# veils_v110.net
KiCad netlist of a schematic drawn in EAGLE
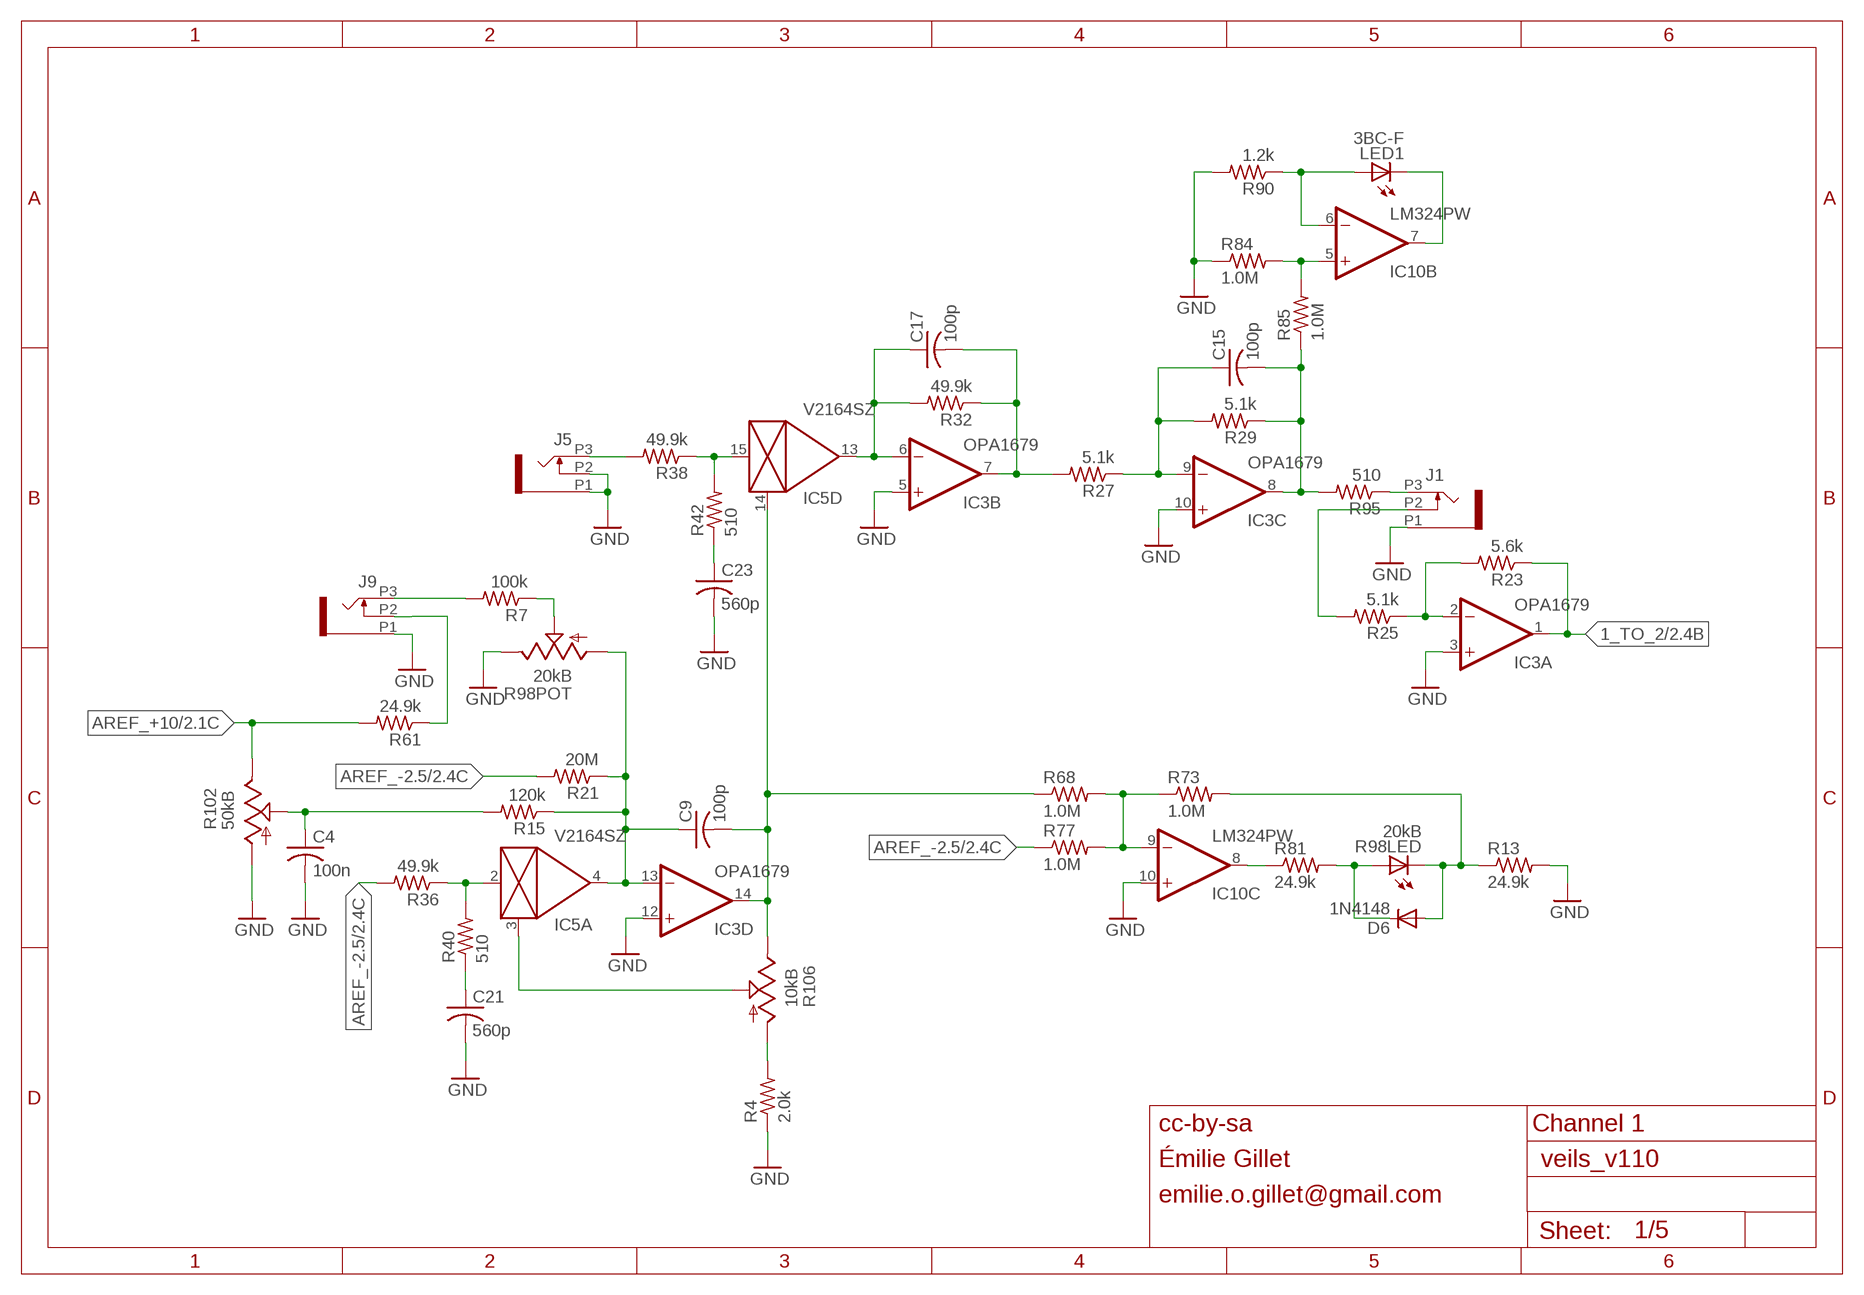
[diagram p0: schematic, sheet 1]
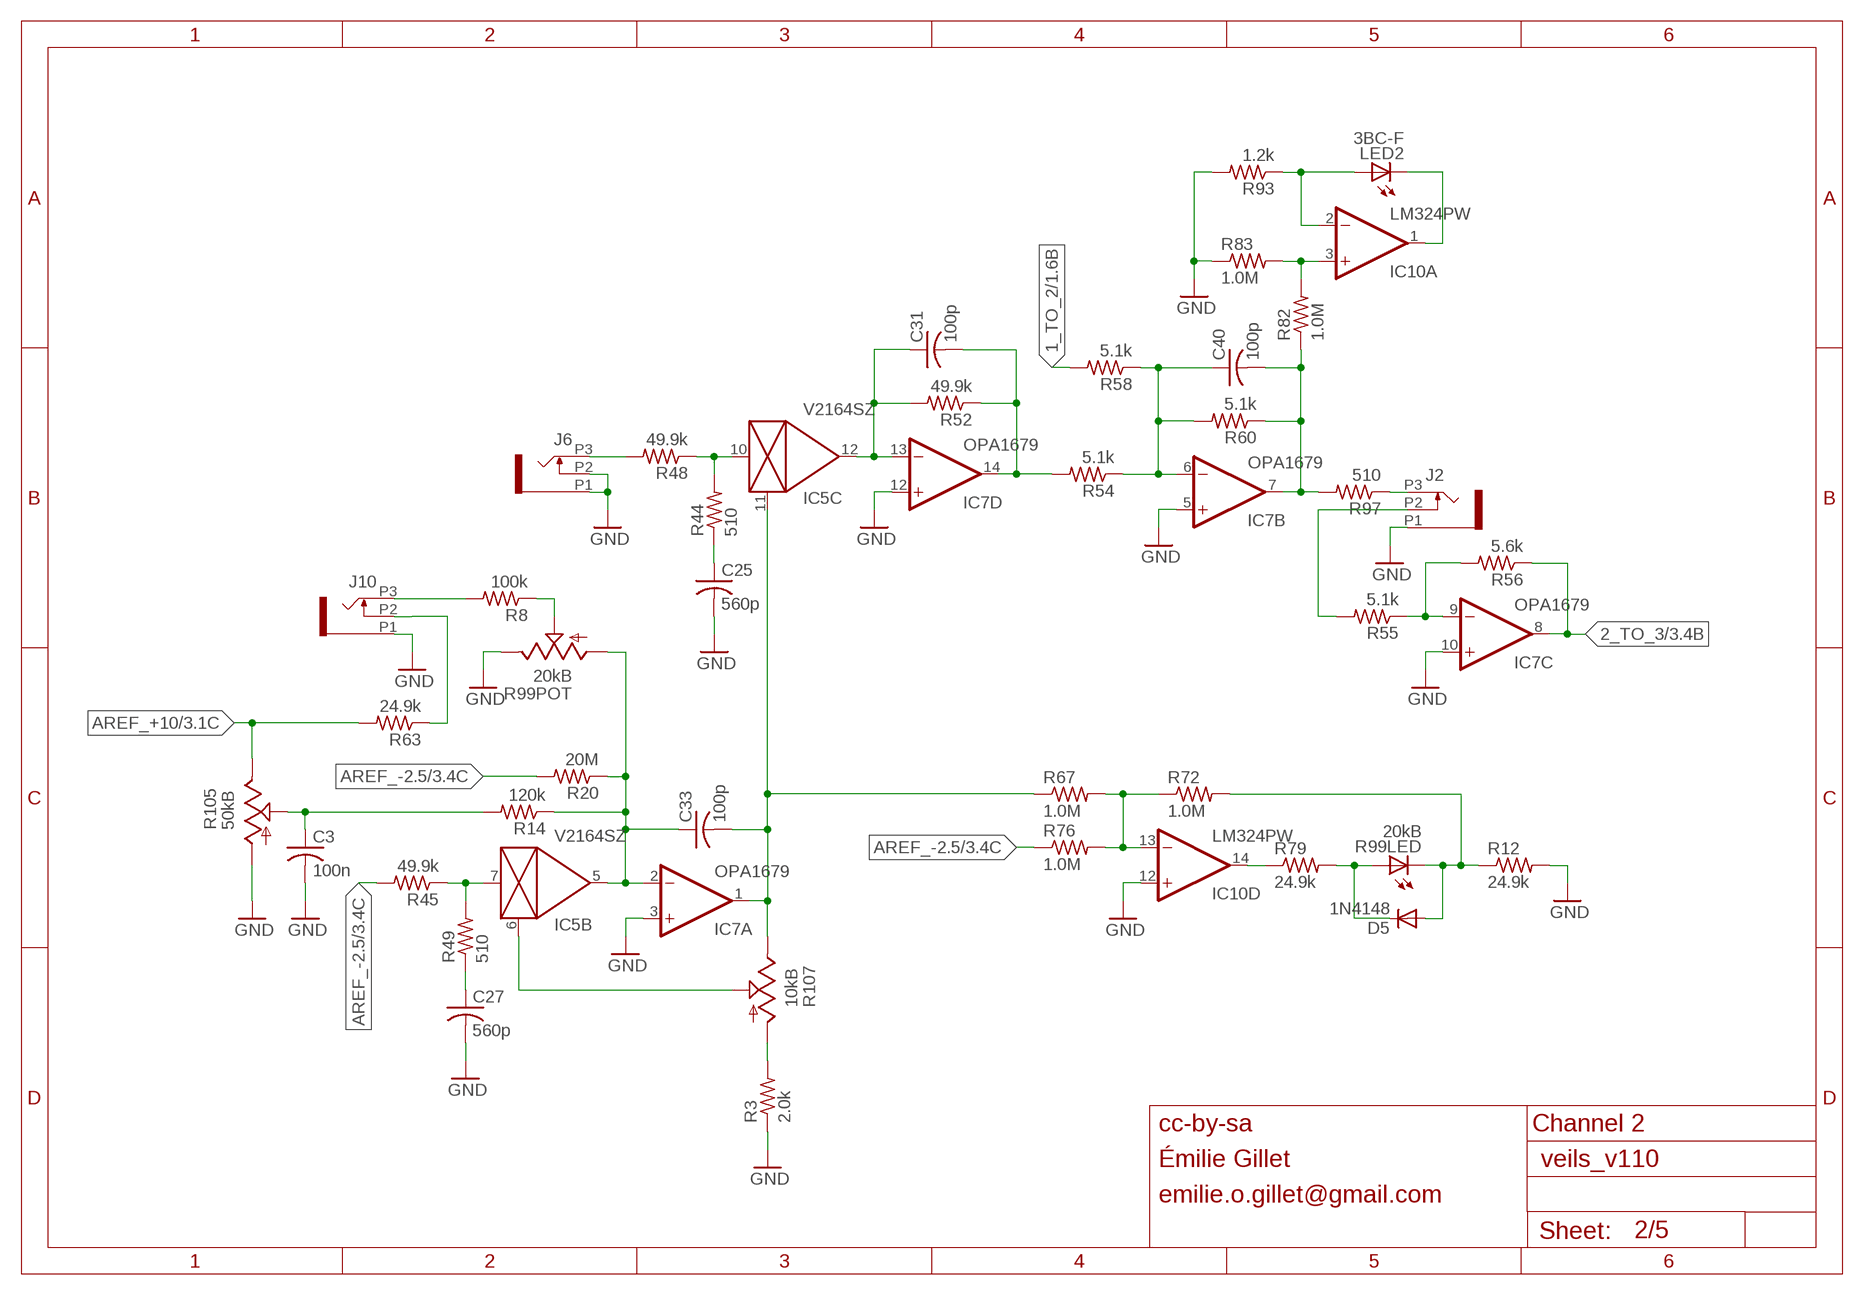
[diagram p1: schematic, sheet 2]
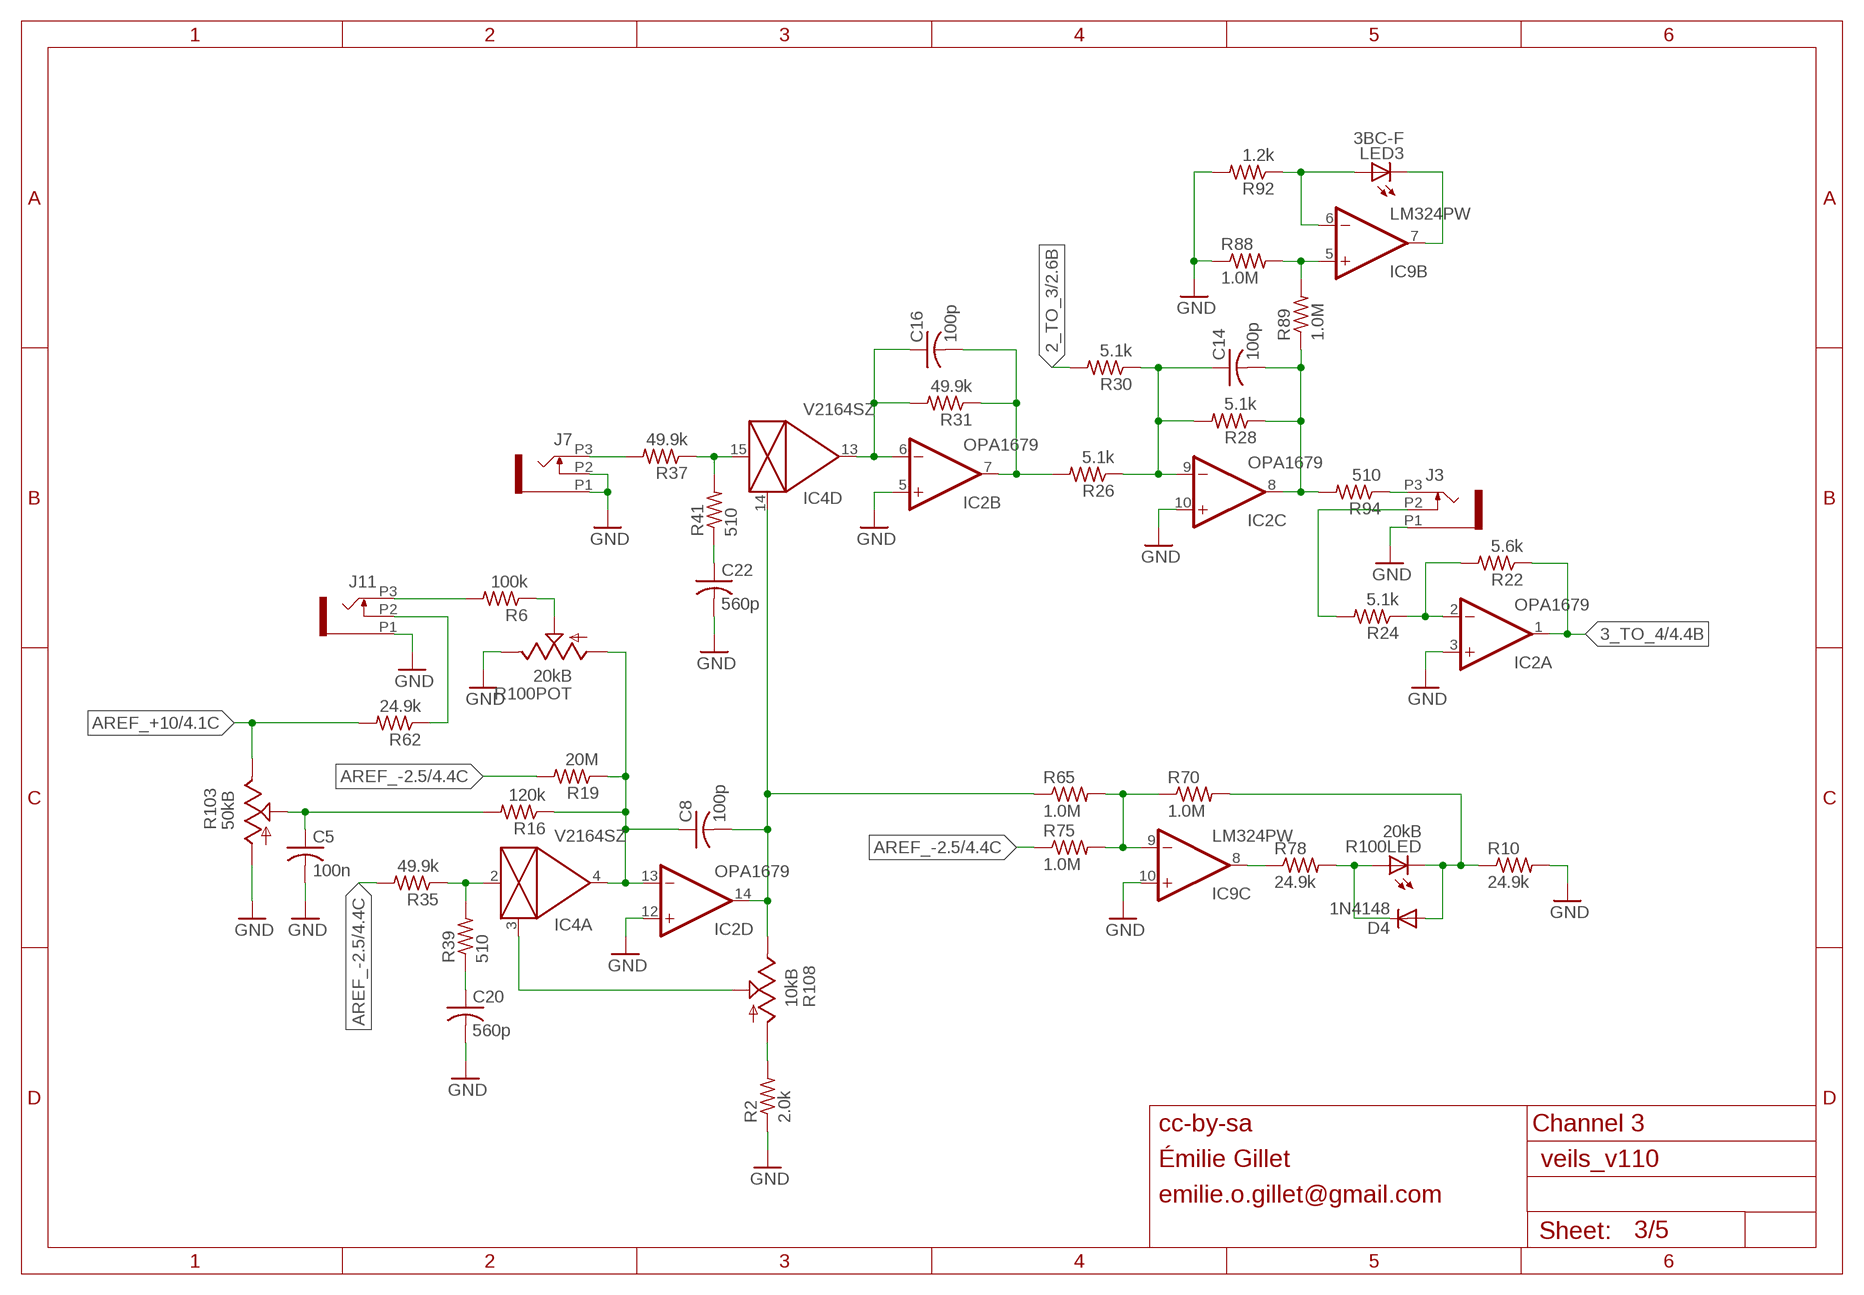
[diagram p2: schematic, sheet 3]
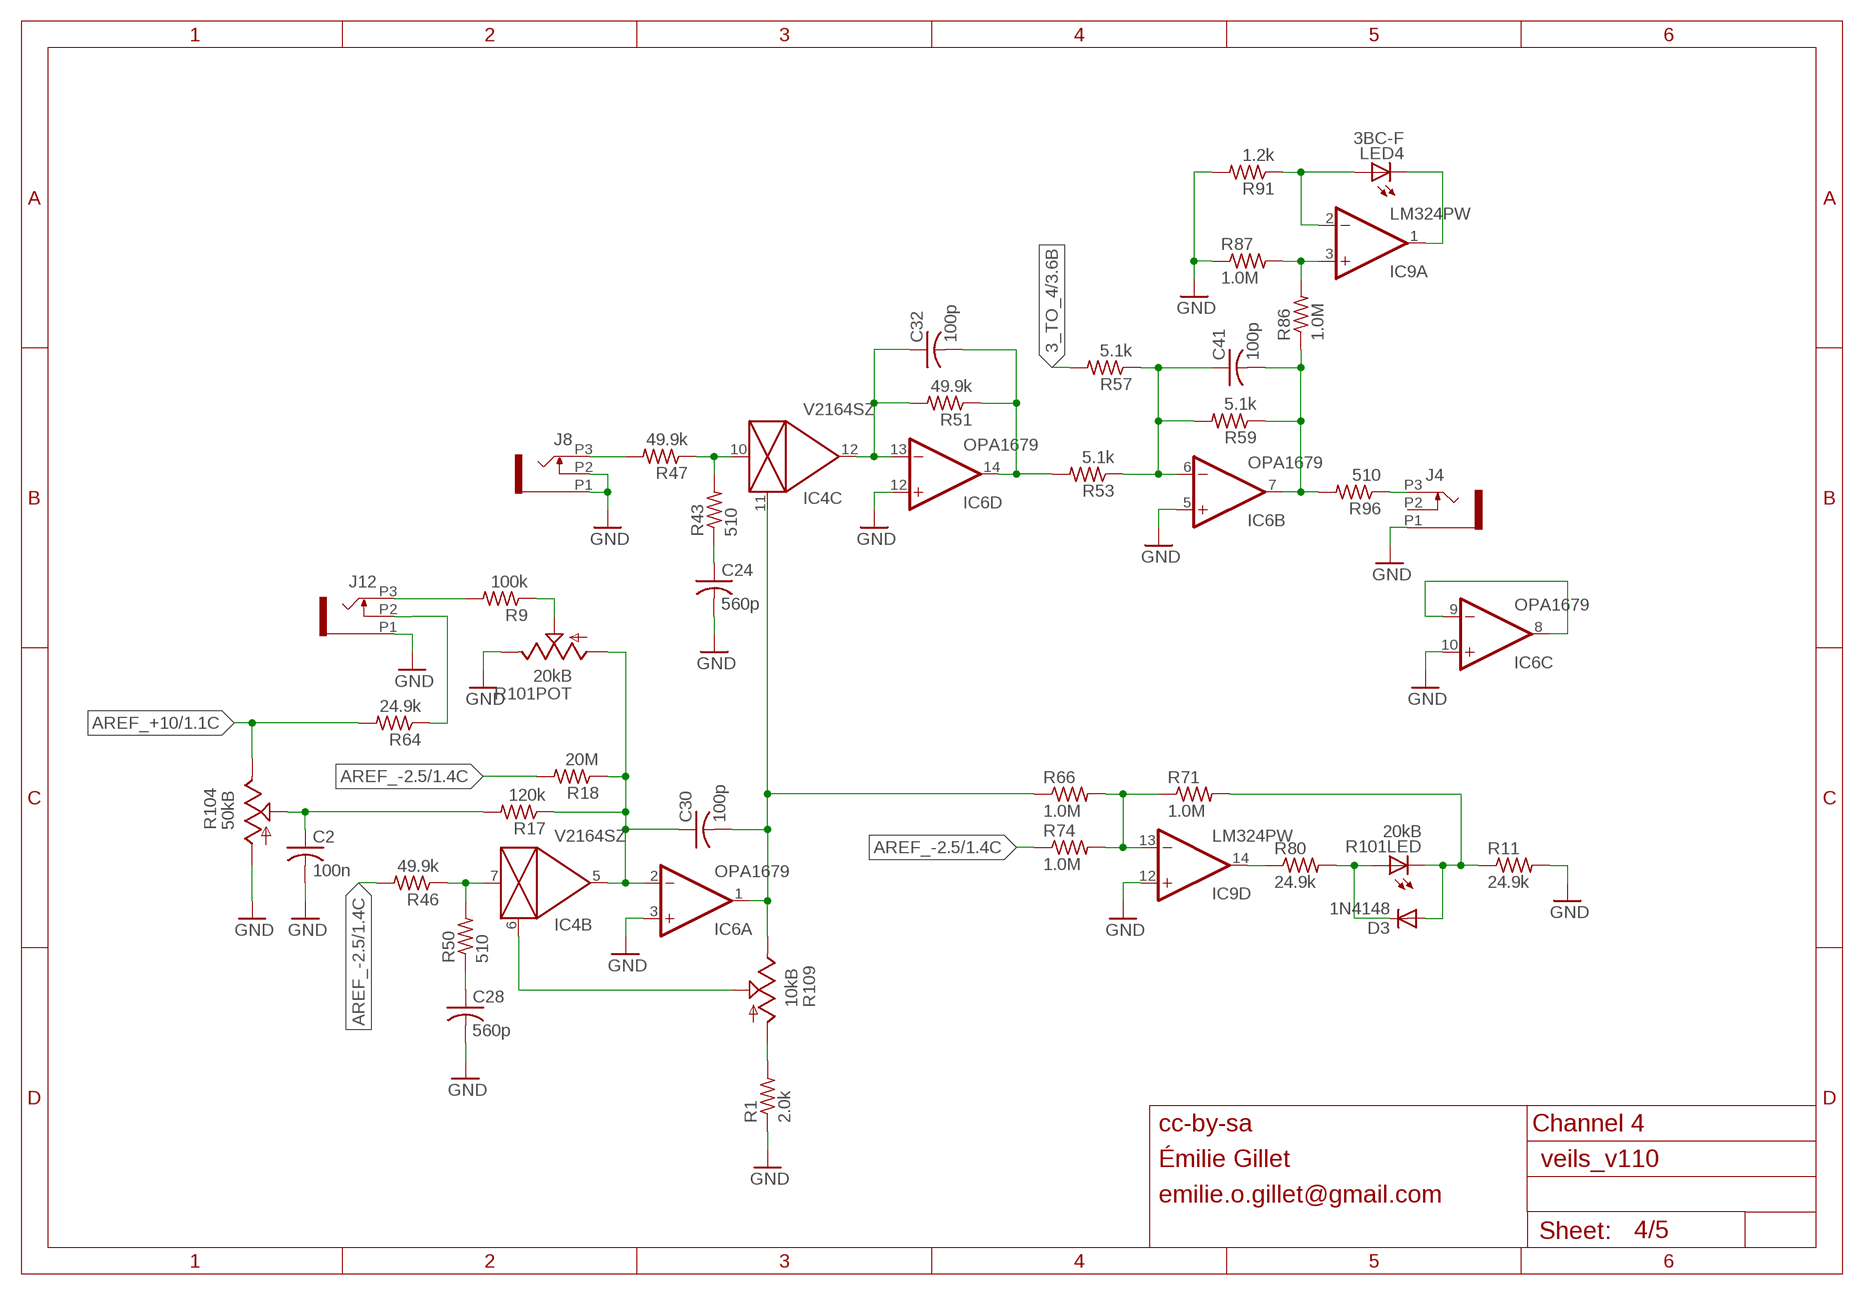
[diagram p3: schematic, sheet 4]
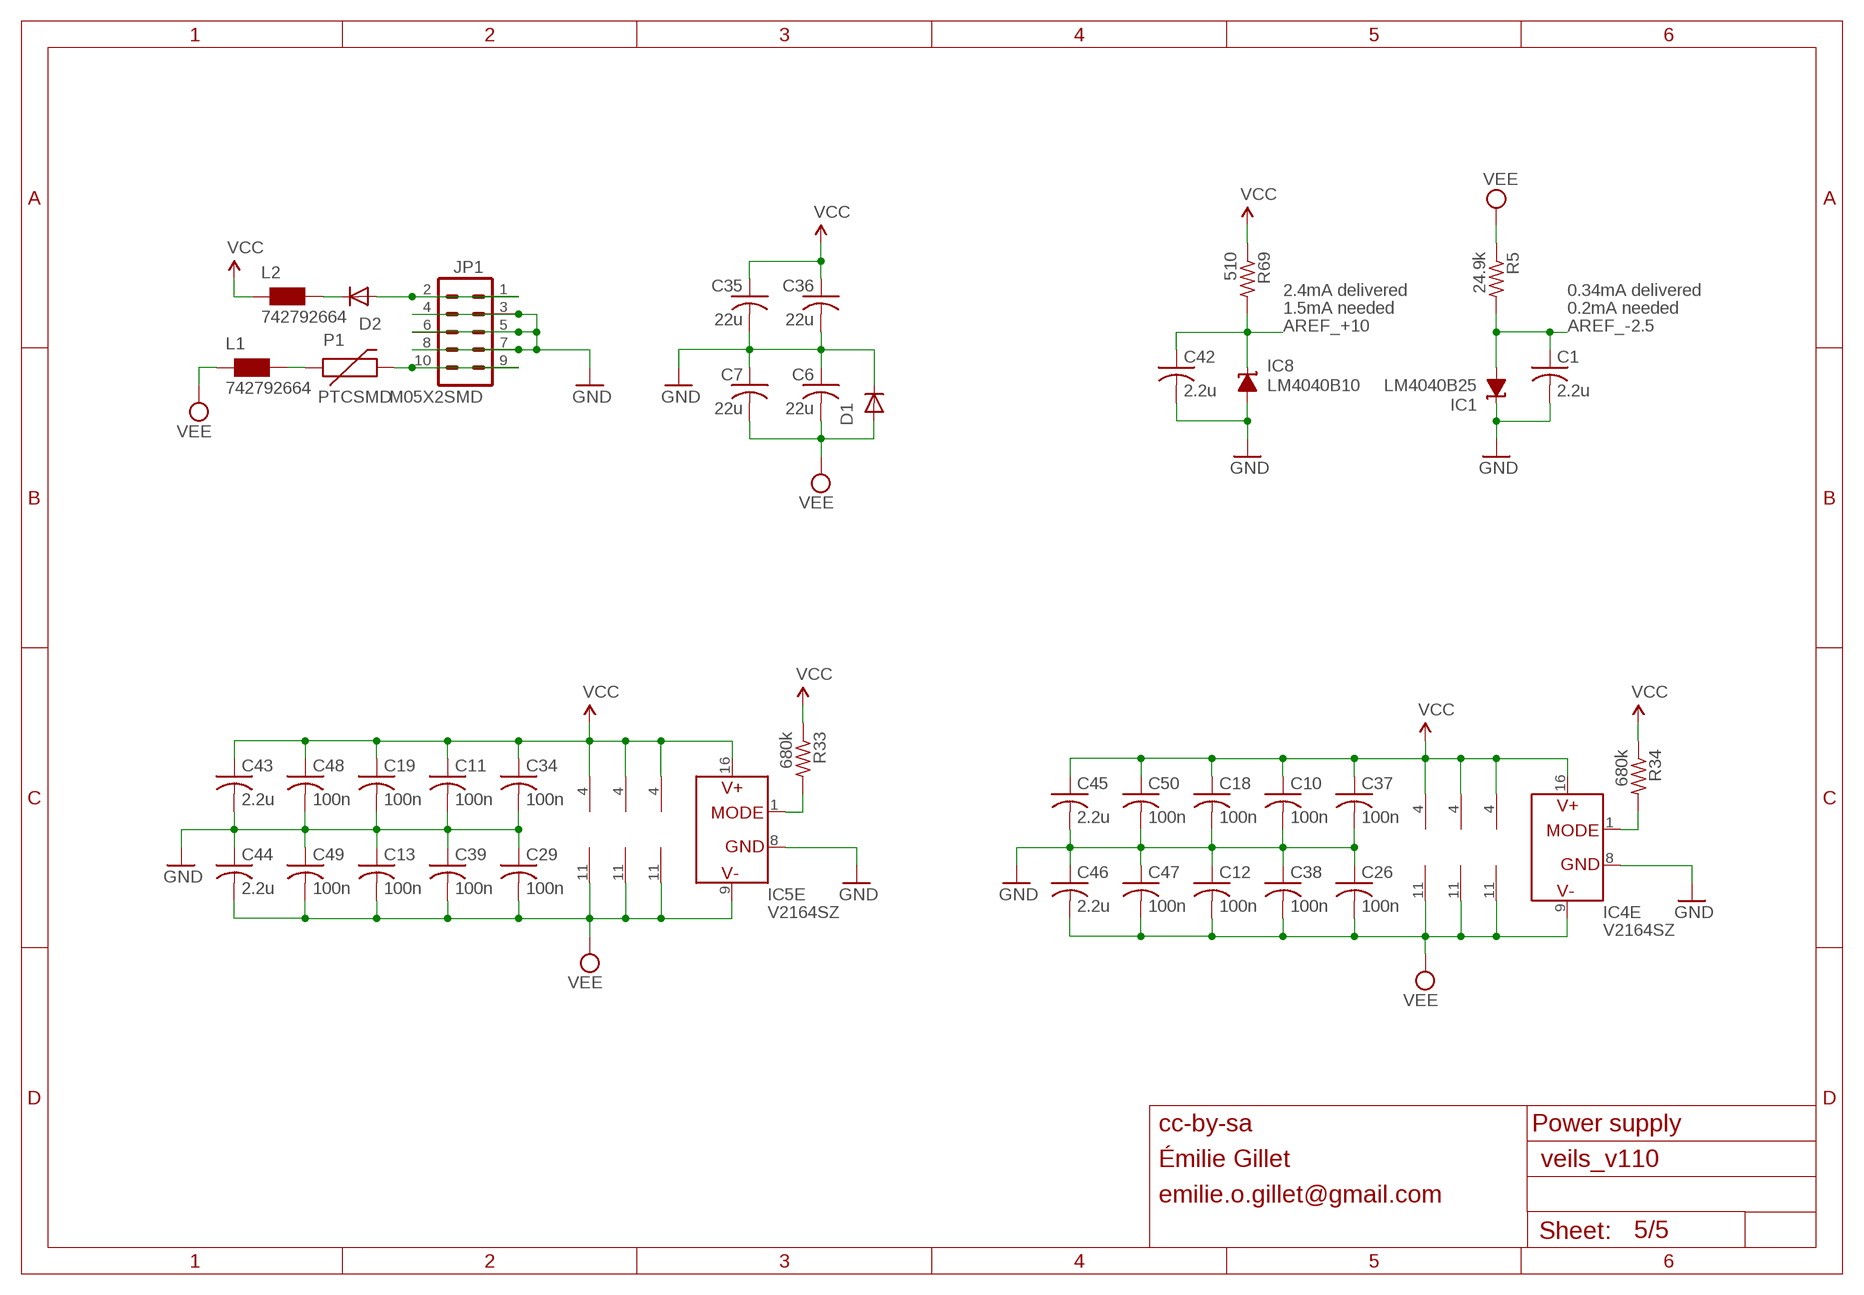
[diagram p4: schematic, sheet 5]

(export (version "E")
  (design (tool "Eeschema 10.0.6"))
  (components
    (comp (ref "C3")
      (value "100n")
      (footprint "eagle-import:C0402")
      (libsource (lib "eagle-import") (part "C-USC0402"))
    )
    (comp (ref "C25")
      (value "560p")
      (footprint "eagle-import:C0402")
      (libsource (lib "eagle-import") (part "C-USC0402"))
    )
    (comp (ref "C27")
      (value "560p")
      (footprint "eagle-import:C0402")
      (libsource (lib "eagle-import") (part "C-USC0402"))
    )
    (comp (ref "C31")
      (value "100p")
      (footprint "eagle-import:C0402")
      (libsource (lib "eagle-import") (part "C-USC0402"))
    )
    (comp (ref "C33")
      (value "100p")
      (footprint "eagle-import:C0402")
      (libsource (lib "eagle-import") (part "C-USC0402"))
    )
    (comp (ref "C40")
      (value "100p")
      (footprint "eagle-import:C0402")
      (libsource (lib "eagle-import") (part "C-USC0402"))
    )
    (comp (ref "D5")
      (value "1N4148")
      (footprint "eagle-import:SOD523")
      (libsource (lib "eagle-import") (part "DIODE-SOD523"))
    )
    (comp (ref "IC5")
      (value "V2164SZ")
      (footprint "eagle-import:SOIC16N")
      (libsource (lib "eagle-import") (part "SSM2164S"))
    )
    (comp (ref "IC7")
      (value "OPA1679")
      (footprint "eagle-import:TSSOP14_065")
      (libsource (lib "eagle-import") (part "OPA1679PW"))
    )
    (comp (ref "IC10")
      (value "LM324PW")
      (footprint "eagle-import:TSSOP14_065")
      (libsource (lib "eagle-import") (part "TL074PW"))
    )
    (comp (ref "J2")
      (value "PJ301_THONKICONNTME")
      (footprint "eagle-import:WQP_PJ_301M_TME")
      (libsource (lib "eagle-import") (part "PJ301_THONKICONNTME"))
    )
    (comp (ref "J6")
      (value "PJ301_THONKICONNTME")
      (footprint "eagle-import:WQP_PJ_301M_TME")
      (libsource (lib "eagle-import") (part "PJ301_THONKICONNTME"))
    )
    (comp (ref "J10")
      (value "PJ301_THONKICONNTME")
      (footprint "eagle-import:WQP_PJ_301M_TME")
      (libsource (lib "eagle-import") (part "PJ301_THONKICONNTME"))
    )
    (comp (ref "LED2")
      (value "3BC-F")
      (footprint "eagle-import:LED3MM")
      (libsource (lib "eagle-import") (part "LED3MM"))
    )
    (comp (ref "R3")
      (value "2.0k")
      (footprint "eagle-import:R0402")
      (libsource (lib "eagle-import") (part "R-US_R0402"))
    )
    (comp (ref "R8")
      (value "100k")
      (footprint "eagle-import:R0402")
      (libsource (lib "eagle-import") (part "R-US_R0402"))
    )
    (comp (ref "R12")
      (value "24.9k")
      (footprint "eagle-import:R0402")
      (libsource (lib "eagle-import") (part "R-US_R0402"))
    )
    (comp (ref "R14")
      (value "120k")
      (footprint "eagle-import:R0402")
      (libsource (lib "eagle-import") (part "R-US_R0402"))
    )
    (comp (ref "R20")
      (value "20M")
      (footprint "eagle-import:R0402")
      (libsource (lib "eagle-import") (part "R-US_R0402"))
    )
    (comp (ref "R44")
      (value "510")
      (footprint "eagle-import:R0402")
      (libsource (lib "eagle-import") (part "R-US_R0402"))
    )
    (comp (ref "R45")
      (value "49.9k")
      (footprint "eagle-import:R0402")
      (libsource (lib "eagle-import") (part "R-US_R0402"))
    )
    (comp (ref "R48")
      (value "49.9k")
      (footprint "eagle-import:R0402")
      (libsource (lib "eagle-import") (part "R-US_R0402"))
    )
    (comp (ref "R49")
      (value "510")
      (footprint "eagle-import:R0402")
      (libsource (lib "eagle-import") (part "R-US_R0402"))
    )
    (comp (ref "R52")
      (value "49.9k")
      (footprint "eagle-import:R0402")
      (libsource (lib "eagle-import") (part "R-US_R0402"))
    )
    (comp (ref "R54")
      (value "5.1k")
      (footprint "eagle-import:R0402")
      (libsource (lib "eagle-import") (part "R-US_R0402"))
    )
    (comp (ref "R55")
      (value "5.1k")
      (footprint "eagle-import:R0402")
      (libsource (lib "eagle-import") (part "R-US_R0402"))
    )
    (comp (ref "R56")
      (value "5.6k")
      (footprint "eagle-import:R0402")
      (libsource (lib "eagle-import") (part "R-US_R0402"))
    )
    (comp (ref "R58")
      (value "5.1k")
      (footprint "eagle-import:R0402")
      (libsource (lib "eagle-import") (part "R-US_R0402"))
    )
    (comp (ref "R60")
      (value "5.1k")
      (footprint "eagle-import:R0402")
      (libsource (lib "eagle-import") (part "R-US_R0402"))
    )
    (comp (ref "R63")
      (value "24.9k")
      (footprint "eagle-import:R0402")
      (libsource (lib "eagle-import") (part "R-US_R0402"))
    )
    (comp (ref "R67")
      (value "1.0M")
      (footprint "eagle-import:R0402")
      (libsource (lib "eagle-import") (part "R-US_R0402"))
    )
    (comp (ref "R72")
      (value "1.0M")
      (footprint "eagle-import:R0402")
      (libsource (lib "eagle-import") (part "R-US_R0402"))
    )
    (comp (ref "R76")
      (value "1.0M")
      (footprint "eagle-import:R0402")
      (libsource (lib "eagle-import") (part "R-US_R0402"))
    )
    (comp (ref "R79")
      (value "24.9k")
      (footprint "eagle-import:R0402")
      (libsource (lib "eagle-import") (part "R-US_R0402"))
    )
    (comp (ref "R82")
      (value "1.0M")
      (footprint "eagle-import:R0402")
      (libsource (lib "eagle-import") (part "R-US_R0402"))
    )
    (comp (ref "R83")
      (value "1.0M")
      (footprint "eagle-import:R0402")
      (libsource (lib "eagle-import") (part "R-US_R0402"))
    )
    (comp (ref "R93")
      (value "1.2k")
      (footprint "eagle-import:R0402")
      (libsource (lib "eagle-import") (part "R-US_R0402"))
    )
    (comp (ref "R97")
      (value "510")
      (footprint "eagle-import:R0603")
      (libsource (lib "eagle-import") (part "R-US_R0603"))
    )
    (comp (ref "R99")
      (value "20kB")
      (footprint "eagle-import:BOURNS_SLIDER")
      (libsource (lib "eagle-import") (part "BOURNS_SLIDER"))
    )
    (comp (ref "R105")
      (value "50kB")
      (footprint "eagle-import:ALPS_POT_NARROW")
      (libsource (lib "eagle-import") (part "POT_USVERTICAL_NARROW"))
    )
    (comp (ref "R107")
      (value "10kB")
      (footprint "eagle-import:ALPS_POT_NARROW")
      (libsource (lib "eagle-import") (part "POT_USVERTICAL_NARROW"))
    )
    (comp (ref "C5")
      (value "100n")
      (footprint "eagle-import:C0402")
      (libsource (lib "eagle-import") (part "C-USC0402"))
    )
    (comp (ref "C8")
      (value "100p")
      (footprint "eagle-import:C0402")
      (libsource (lib "eagle-import") (part "C-USC0402"))
    )
    (comp (ref "C14")
      (value "100p")
      (footprint "eagle-import:C0402")
      (libsource (lib "eagle-import") (part "C-USC0402"))
    )
    (comp (ref "C16")
      (value "100p")
      (footprint "eagle-import:C0402")
      (libsource (lib "eagle-import") (part "C-USC0402"))
    )
    (comp (ref "C20")
      (value "560p")
      (footprint "eagle-import:C0402")
      (libsource (lib "eagle-import") (part "C-USC0402"))
    )
    (comp (ref "C22")
      (value "560p")
      (footprint "eagle-import:C0402")
      (libsource (lib "eagle-import") (part "C-USC0402"))
    )
    (comp (ref "D4")
      (value "1N4148")
      (footprint "eagle-import:SOD523")
      (libsource (lib "eagle-import") (part "DIODE-SOD523"))
    )
    (comp (ref "IC2")
      (value "OPA1679")
      (footprint "eagle-import:TSSOP14_065")
      (libsource (lib "eagle-import") (part "OPA1679PW"))
    )
    (comp (ref "IC4")
      (value "V2164SZ")
      (footprint "eagle-import:SOIC16N")
      (libsource (lib "eagle-import") (part "SSM2164S"))
    )
    (comp (ref "IC9")
      (value "LM324PW")
      (footprint "eagle-import:TSSOP14_065")
      (libsource (lib "eagle-import") (part "TL074PW"))
    )
    (comp (ref "J3")
      (value "PJ301_THONKICONNTME")
      (footprint "eagle-import:WQP_PJ_301M_TME")
      (libsource (lib "eagle-import") (part "PJ301_THONKICONNTME"))
    )
    (comp (ref "J7")
      (value "PJ301_THONKICONNTME")
      (footprint "eagle-import:WQP_PJ_301M_TME")
      (libsource (lib "eagle-import") (part "PJ301_THONKICONNTME"))
    )
    (comp (ref "J11")
      (value "PJ301_THONKICONNTME")
      (footprint "eagle-import:WQP_PJ_301M_TME")
      (libsource (lib "eagle-import") (part "PJ301_THONKICONNTME"))
    )
    (comp (ref "LED3")
      (value "3BC-F")
      (footprint "eagle-import:LED3MM")
      (libsource (lib "eagle-import") (part "LED3MM"))
    )
    (comp (ref "R2")
      (value "2.0k")
      (footprint "eagle-import:R0402")
      (libsource (lib "eagle-import") (part "R-US_R0402"))
    )
    (comp (ref "R6")
      (value "100k")
      (footprint "eagle-import:R0402")
      (libsource (lib "eagle-import") (part "R-US_R0402"))
    )
    (comp (ref "R10")
      (value "24.9k")
      (footprint "eagle-import:R0402")
      (libsource (lib "eagle-import") (part "R-US_R0402"))
    )
    (comp (ref "R16")
      (value "120k")
      (footprint "eagle-import:R0402")
      (libsource (lib "eagle-import") (part "R-US_R0402"))
    )
    (comp (ref "R19")
      (value "20M")
      (footprint "eagle-import:R0402")
      (libsource (lib "eagle-import") (part "R-US_R0402"))
    )
    (comp (ref "R22")
      (value "5.6k")
      (footprint "eagle-import:R0402")
      (libsource (lib "eagle-import") (part "R-US_R0402"))
    )
    (comp (ref "R24")
      (value "5.1k")
      (footprint "eagle-import:R0402")
      (libsource (lib "eagle-import") (part "R-US_R0402"))
    )
    (comp (ref "R26")
      (value "5.1k")
      (footprint "eagle-import:R0402")
      (libsource (lib "eagle-import") (part "R-US_R0402"))
    )
    (comp (ref "R28")
      (value "5.1k")
      (footprint "eagle-import:R0402")
      (libsource (lib "eagle-import") (part "R-US_R0402"))
    )
    (comp (ref "R30")
      (value "5.1k")
      (footprint "eagle-import:R0402")
      (libsource (lib "eagle-import") (part "R-US_R0402"))
    )
    (comp (ref "R31")
      (value "49.9k")
      (footprint "eagle-import:R0402")
      (libsource (lib "eagle-import") (part "R-US_R0402"))
    )
    (comp (ref "R35")
      (value "49.9k")
      (footprint "eagle-import:R0402")
      (libsource (lib "eagle-import") (part "R-US_R0402"))
    )
    (comp (ref "R37")
      (value "49.9k")
      (footprint "eagle-import:R0402")
      (libsource (lib "eagle-import") (part "R-US_R0402"))
    )
    (comp (ref "R39")
      (value "510")
      (footprint "eagle-import:R0402")
      (libsource (lib "eagle-import") (part "R-US_R0402"))
    )
    (comp (ref "R41")
      (value "510")
      (footprint "eagle-import:R0402")
      (libsource (lib "eagle-import") (part "R-US_R0402"))
    )
    (comp (ref "R62")
      (value "24.9k")
      (footprint "eagle-import:R0402")
      (libsource (lib "eagle-import") (part "R-US_R0402"))
    )
    (comp (ref "R65")
      (value "1.0M")
      (footprint "eagle-import:R0402")
      (libsource (lib "eagle-import") (part "R-US_R0402"))
    )
    (comp (ref "R70")
      (value "1.0M")
      (footprint "eagle-import:R0402")
      (libsource (lib "eagle-import") (part "R-US_R0402"))
    )
    (comp (ref "R75")
      (value "1.0M")
      (footprint "eagle-import:R0402")
      (libsource (lib "eagle-import") (part "R-US_R0402"))
    )
    (comp (ref "R78")
      (value "24.9k")
      (footprint "eagle-import:R0402")
      (libsource (lib "eagle-import") (part "R-US_R0402"))
    )
    (comp (ref "R88")
      (value "1.0M")
      (footprint "eagle-import:R0402")
      (libsource (lib "eagle-import") (part "R-US_R0402"))
    )
    (comp (ref "R89")
      (value "1.0M")
      (footprint "eagle-import:R0402")
      (libsource (lib "eagle-import") (part "R-US_R0402"))
    )
    (comp (ref "R92")
      (value "1.2k")
      (footprint "eagle-import:R0402")
      (libsource (lib "eagle-import") (part "R-US_R0402"))
    )
    (comp (ref "R94")
      (value "510")
      (footprint "eagle-import:R0603")
      (libsource (lib "eagle-import") (part "R-US_R0603"))
    )
    (comp (ref "R100")
      (value "20kB")
      (footprint "eagle-import:BOURNS_SLIDER")
      (libsource (lib "eagle-import") (part "BOURNS_SLIDER"))
    )
    (comp (ref "R103")
      (value "50kB")
      (footprint "eagle-import:ALPS_POT_NARROW")
      (libsource (lib "eagle-import") (part "POT_USVERTICAL_NARROW"))
    )
    (comp (ref "R108")
      (value "10kB")
      (footprint "eagle-import:ALPS_POT_NARROW")
      (libsource (lib "eagle-import") (part "POT_USVERTICAL_NARROW"))
    )
    (comp (ref "C1")
      (value "2.2u")
      (footprint "eagle-import:C0603")
      (libsource (lib "eagle-import") (part "C-USC0603"))
    )
    (comp (ref "C6")
      (value "22u")
      (footprint "eagle-import:C1206")
      (libsource (lib "eagle-import") (part "C-USC1206"))
    )
    (comp (ref "C7")
      (value "22u")
      (footprint "eagle-import:C1206")
      (libsource (lib "eagle-import") (part "C-USC1206"))
    )
    (comp (ref "C10")
      (value "100n")
      (footprint "eagle-import:C0402")
      (libsource (lib "eagle-import") (part "C-USC0402"))
    )
    (comp (ref "C11")
      (value "100n")
      (footprint "eagle-import:C0402")
      (libsource (lib "eagle-import") (part "C-USC0402"))
    )
    (comp (ref "C12")
      (value "100n")
      (footprint "eagle-import:C0402")
      (libsource (lib "eagle-import") (part "C-USC0402"))
    )
    (comp (ref "C13")
      (value "100n")
      (footprint "eagle-import:C0402")
      (libsource (lib "eagle-import") (part "C-USC0402"))
    )
    (comp (ref "C18")
      (value "100n")
      (footprint "eagle-import:C0402")
      (libsource (lib "eagle-import") (part "C-USC0402"))
    )
    (comp (ref "C19")
      (value "100n")
      (footprint "eagle-import:C0402")
      (libsource (lib "eagle-import") (part "C-USC0402"))
    )
    (comp (ref "C26")
      (value "100n")
      (footprint "eagle-import:C0402")
      (libsource (lib "eagle-import") (part "C-USC0402"))
    )
    (comp (ref "C29")
      (value "100n")
      (footprint "eagle-import:C0402")
      (libsource (lib "eagle-import") (part "C-USC0402"))
    )
    (comp (ref "C34")
      (value "100n")
      (footprint "eagle-import:C0402")
      (libsource (lib "eagle-import") (part "C-USC0402"))
    )
    (comp (ref "C35")
      (value "22u")
      (footprint "eagle-import:C1206")
      (libsource (lib "eagle-import") (part "C-USC1206"))
    )
    (comp (ref "C36")
      (value "22u")
      (footprint "eagle-import:C1206")
      (libsource (lib "eagle-import") (part "C-USC1206"))
    )
    (comp (ref "C37")
      (value "100n")
      (footprint "eagle-import:C0402")
      (libsource (lib "eagle-import") (part "C-USC0402"))
    )
    (comp (ref "C38")
      (value "100n")
      (footprint "eagle-import:C0402")
      (libsource (lib "eagle-import") (part "C-USC0402"))
    )
    (comp (ref "C39")
      (value "100n")
      (footprint "eagle-import:C0402")
      (libsource (lib "eagle-import") (part "C-USC0402"))
    )
    (comp (ref "C42")
      (value "2.2u")
      (footprint "eagle-import:C0603")
      (libsource (lib "eagle-import") (part "C-USC0603"))
    )
    (comp (ref "C43")
      (value "2.2u")
      (footprint "eagle-import:C0603")
      (libsource (lib "eagle-import") (part "C-USC0603"))
    )
    (comp (ref "C44")
      (value "2.2u")
      (footprint "eagle-import:C0603")
      (libsource (lib "eagle-import") (part "C-USC0603"))
    )
    (comp (ref "C45")
      (value "2.2u")
      (footprint "eagle-import:C0603")
      (libsource (lib "eagle-import") (part "C-USC0603"))
    )
    (comp (ref "C46")
      (value "2.2u")
      (footprint "eagle-import:C0603")
      (libsource (lib "eagle-import") (part "C-USC0603"))
    )
    (comp (ref "C47")
      (value "100n")
      (footprint "eagle-import:C0402")
      (libsource (lib "eagle-import") (part "C-USC0402"))
    )
    (comp (ref "C48")
      (value "100n")
      (footprint "eagle-import:C0402")
      (libsource (lib "eagle-import") (part "C-USC0402"))
    )
    (comp (ref "C49")
      (value "100n")
      (footprint "eagle-import:C0402")
      (libsource (lib "eagle-import") (part "C-USC0402"))
    )
    (comp (ref "C50")
      (value "100n")
      (footprint "eagle-import:C0402")
      (libsource (lib "eagle-import") (part "C-USC0402"))
    )
    (comp (ref "D1")
      (value "1N5819HW")
      (footprint "eagle-import:SOD123")
      (libsource (lib "eagle-import") (part "DIODE-SOD123"))
    )
    (comp (ref "D2")
      (value "1N5819HW")
      (footprint "eagle-import:SOD123")
      (libsource (lib "eagle-import") (part "DIODE-SOD123"))
    )
    (comp (ref "IC1")
      (value "LM4040B25")
      (footprint "eagle-import:DBZ_R-PDSO-G3")
      (libsource (lib "eagle-import") (part "LM4041DBZB12"))
    )
    (comp (ref "IC3")
      (value "OPA1679")
      (footprint "eagle-import:TSSOP14_065")
      (libsource (lib "eagle-import") (part "OPA1679PW"))
    )
    (comp (ref "IC6")
      (value "OPA1679")
      (footprint "eagle-import:TSSOP14_065")
      (libsource (lib "eagle-import") (part "OPA1679PW"))
    )
    (comp (ref "IC8")
      (value "LM4040B10")
      (footprint "eagle-import:DBZ_R-PDSO-G3")
      (libsource (lib "eagle-import") (part "LM4041DBZB12"))
    )
    (comp (ref "JP1")
      (value "M05X2SMD")
      (footprint "eagle-import:2X5-SMD")
      (libsource (lib "eagle-import") (part "M05X2SMD"))
    )
    (comp (ref "L1")
      (value "742792664")
      (footprint "eagle-import:0603")
      (libsource (lib "eagle-import") (part "WE-CBF_0603"))
    )
    (comp (ref "L2")
      (value "742792664")
      (footprint "eagle-import:0603")
      (libsource (lib "eagle-import") (part "WE-CBF_0603"))
    )
    (comp (ref "P1")
      (value "PTCSMD")
      (footprint "eagle-import:PTC-1206")
      (libsource (lib "eagle-import") (part "PTCSMD"))
    )
    (comp (ref "R5")
      (value "24.9k")
      (footprint "eagle-import:R0402")
      (libsource (lib "eagle-import") (part "R-US_R0402"))
    )
    (comp (ref "R33")
      (value "680k")
      (footprint "eagle-import:R0402")
      (libsource (lib "eagle-import") (part "R-US_R0402"))
    )
    (comp (ref "R34")
      (value "680k")
      (footprint "eagle-import:R0402")
      (libsource (lib "eagle-import") (part "R-US_R0402"))
    )
    (comp (ref "R69")
      (value "510")
      (footprint "eagle-import:R0402")
      (libsource (lib "eagle-import") (part "R-US_R0402"))
    )
    (comp (ref "C4")
      (value "100n")
      (footprint "eagle-import:C0402")
      (libsource (lib "eagle-import") (part "C-USC0402"))
    )
    (comp (ref "C9")
      (value "100p")
      (footprint "eagle-import:C0402")
      (libsource (lib "eagle-import") (part "C-USC0402"))
    )
    (comp (ref "C15")
      (value "100p")
      (footprint "eagle-import:C0402")
      (libsource (lib "eagle-import") (part "C-USC0402"))
    )
    (comp (ref "C17")
      (value "100p")
      (footprint "eagle-import:C0402")
      (libsource (lib "eagle-import") (part "C-USC0402"))
    )
    (comp (ref "C21")
      (value "560p")
      (footprint "eagle-import:C0402")
      (libsource (lib "eagle-import") (part "C-USC0402"))
    )
    (comp (ref "C23")
      (value "560p")
      (footprint "eagle-import:C0402")
      (libsource (lib "eagle-import") (part "C-USC0402"))
    )
    (comp (ref "D6")
      (value "1N4148")
      (footprint "eagle-import:SOD523")
      (libsource (lib "eagle-import") (part "DIODE-SOD523"))
    )
    (comp (ref "J1")
      (value "PJ301_THONKICONNTME")
      (footprint "eagle-import:WQP_PJ_301M_TME")
      (libsource (lib "eagle-import") (part "PJ301_THONKICONNTME"))
    )
    (comp (ref "J5")
      (value "PJ301_THONKICONNTME")
      (footprint "eagle-import:WQP_PJ_301M_TME")
      (libsource (lib "eagle-import") (part "PJ301_THONKICONNTME"))
    )
    (comp (ref "J9")
      (value "PJ301_THONKICONNTME")
      (footprint "eagle-import:WQP_PJ_301M_TME")
      (libsource (lib "eagle-import") (part "PJ301_THONKICONNTME"))
    )
    (comp (ref "LED1")
      (value "3BC-F")
      (footprint "eagle-import:LED3MM")
      (libsource (lib "eagle-import") (part "LED3MM"))
    )
    (comp (ref "R4")
      (value "2.0k")
      (footprint "eagle-import:R0402")
      (libsource (lib "eagle-import") (part "R-US_R0402"))
    )
    (comp (ref "R7")
      (value "100k")
      (footprint "eagle-import:R0402")
      (libsource (lib "eagle-import") (part "R-US_R0402"))
    )
    (comp (ref "R13")
      (value "24.9k")
      (footprint "eagle-import:R0402")
      (libsource (lib "eagle-import") (part "R-US_R0402"))
    )
    (comp (ref "R15")
      (value "120k")
      (footprint "eagle-import:R0402")
      (libsource (lib "eagle-import") (part "R-US_R0402"))
    )
    (comp (ref "R21")
      (value "20M")
      (footprint "eagle-import:R0402")
      (libsource (lib "eagle-import") (part "R-US_R0402"))
    )
    (comp (ref "R23")
      (value "5.6k")
      (footprint "eagle-import:R0402")
      (libsource (lib "eagle-import") (part "R-US_R0402"))
    )
    (comp (ref "R25")
      (value "5.1k")
      (footprint "eagle-import:R0402")
      (libsource (lib "eagle-import") (part "R-US_R0402"))
    )
    (comp (ref "R27")
      (value "5.1k")
      (footprint "eagle-import:R0402")
      (libsource (lib "eagle-import") (part "R-US_R0402"))
    )
    (comp (ref "R29")
      (value "5.1k")
      (footprint "eagle-import:R0402")
      (libsource (lib "eagle-import") (part "R-US_R0402"))
    )
    (comp (ref "R32")
      (value "49.9k")
      (footprint "eagle-import:R0402")
      (libsource (lib "eagle-import") (part "R-US_R0402"))
    )
    (comp (ref "R36")
      (value "49.9k")
      (footprint "eagle-import:R0402")
      (libsource (lib "eagle-import") (part "R-US_R0402"))
    )
    (comp (ref "R38")
      (value "49.9k")
      (footprint "eagle-import:R0402")
      (libsource (lib "eagle-import") (part "R-US_R0402"))
    )
    (comp (ref "R40")
      (value "510")
      (footprint "eagle-import:R0402")
      (libsource (lib "eagle-import") (part "R-US_R0402"))
    )
    (comp (ref "R42")
      (value "510")
      (footprint "eagle-import:R0402")
      (libsource (lib "eagle-import") (part "R-US_R0402"))
    )
    (comp (ref "R61")
      (value "24.9k")
      (footprint "eagle-import:R0402")
      (libsource (lib "eagle-import") (part "R-US_R0402"))
    )
    (comp (ref "R68")
      (value "1.0M")
      (footprint "eagle-import:R0402")
      (libsource (lib "eagle-import") (part "R-US_R0402"))
    )
    (comp (ref "R73")
      (value "1.0M")
      (footprint "eagle-import:R0402")
      (libsource (lib "eagle-import") (part "R-US_R0402"))
    )
    (comp (ref "R77")
      (value "1.0M")
      (footprint "eagle-import:R0402")
      (libsource (lib "eagle-import") (part "R-US_R0402"))
    )
    (comp (ref "R81")
      (value "24.9k")
      (footprint "eagle-import:R0402")
      (libsource (lib "eagle-import") (part "R-US_R0402"))
    )
    (comp (ref "R84")
      (value "1.0M")
      (footprint "eagle-import:R0402")
      (libsource (lib "eagle-import") (part "R-US_R0402"))
    )
    (comp (ref "R85")
      (value "1.0M")
      (footprint "eagle-import:R0402")
      (libsource (lib "eagle-import") (part "R-US_R0402"))
    )
    (comp (ref "R90")
      (value "1.2k")
      (footprint "eagle-import:R0402")
      (libsource (lib "eagle-import") (part "R-US_R0402"))
    )
    (comp (ref "R95")
      (value "510")
      (footprint "eagle-import:R0603")
      (libsource (lib "eagle-import") (part "R-US_R0603"))
    )
    (comp (ref "R98")
      (value "20kB")
      (footprint "eagle-import:BOURNS_SLIDER")
      (libsource (lib "eagle-import") (part "BOURNS_SLIDER"))
    )
    (comp (ref "R102")
      (value "50kB")
      (footprint "eagle-import:ALPS_POT_NARROW")
      (libsource (lib "eagle-import") (part "POT_USVERTICAL_NARROW"))
    )
    (comp (ref "R106")
      (value "10kB")
      (footprint "eagle-import:ALPS_POT_NARROW")
      (libsource (lib "eagle-import") (part "POT_USVERTICAL_NARROW"))
    )
    (comp (ref "C2")
      (value "100n")
      (footprint "eagle-import:C0402")
      (libsource (lib "eagle-import") (part "C-USC0402"))
    )
    (comp (ref "C24")
      (value "560p")
      (footprint "eagle-import:C0402")
      (libsource (lib "eagle-import") (part "C-USC0402"))
    )
    (comp (ref "C28")
      (value "560p")
      (footprint "eagle-import:C0402")
      (libsource (lib "eagle-import") (part "C-USC0402"))
    )
    (comp (ref "C30")
      (value "100p")
      (footprint "eagle-import:C0402")
      (libsource (lib "eagle-import") (part "C-USC0402"))
    )
    (comp (ref "C32")
      (value "100p")
      (footprint "eagle-import:C0402")
      (libsource (lib "eagle-import") (part "C-USC0402"))
    )
    (comp (ref "C41")
      (value "100p")
      (footprint "eagle-import:C0402")
      (libsource (lib "eagle-import") (part "C-USC0402"))
    )
    (comp (ref "D3")
      (value "1N4148")
      (footprint "eagle-import:SOD523")
      (libsource (lib "eagle-import") (part "DIODE-SOD523"))
    )
    (comp (ref "J4")
      (value "PJ301_THONKICONNTME")
      (footprint "eagle-import:WQP_PJ_301M_TME")
      (libsource (lib "eagle-import") (part "PJ301_THONKICONNTME"))
    )
    (comp (ref "J8")
      (value "PJ301_THONKICONNTME")
      (footprint "eagle-import:WQP_PJ_301M_TME")
      (libsource (lib "eagle-import") (part "PJ301_THONKICONNTME"))
    )
    (comp (ref "J12")
      (value "PJ301_THONKICONNTME")
      (footprint "eagle-import:WQP_PJ_301M_TME")
      (libsource (lib "eagle-import") (part "PJ301_THONKICONNTME"))
    )
    (comp (ref "LED4")
      (value "3BC-F")
      (footprint "eagle-import:LED3MM")
      (libsource (lib "eagle-import") (part "LED3MM"))
    )
    (comp (ref "R1")
      (value "2.0k")
      (footprint "eagle-import:R0402")
      (libsource (lib "eagle-import") (part "R-US_R0402"))
    )
    (comp (ref "R9")
      (value "100k")
      (footprint "eagle-import:R0402")
      (libsource (lib "eagle-import") (part "R-US_R0402"))
    )
    (comp (ref "R11")
      (value "24.9k")
      (footprint "eagle-import:R0402")
      (libsource (lib "eagle-import") (part "R-US_R0402"))
    )
    (comp (ref "R17")
      (value "120k")
      (footprint "eagle-import:R0402")
      (libsource (lib "eagle-import") (part "R-US_R0402"))
    )
    (comp (ref "R18")
      (value "20M")
      (footprint "eagle-import:R0402")
      (libsource (lib "eagle-import") (part "R-US_R0402"))
    )
    (comp (ref "R43")
      (value "510")
      (footprint "eagle-import:R0402")
      (libsource (lib "eagle-import") (part "R-US_R0402"))
    )
    (comp (ref "R46")
      (value "49.9k")
      (footprint "eagle-import:R0402")
      (libsource (lib "eagle-import") (part "R-US_R0402"))
    )
    (comp (ref "R47")
      (value "49.9k")
      (footprint "eagle-import:R0402")
      (libsource (lib "eagle-import") (part "R-US_R0402"))
    )
    (comp (ref "R50")
      (value "510")
      (footprint "eagle-import:R0402")
      (libsource (lib "eagle-import") (part "R-US_R0402"))
    )
    (comp (ref "R51")
      (value "49.9k")
      (footprint "eagle-import:R0402")
      (libsource (lib "eagle-import") (part "R-US_R0402"))
    )
    (comp (ref "R53")
      (value "5.1k")
      (footprint "eagle-import:R0402")
      (libsource (lib "eagle-import") (part "R-US_R0402"))
    )
    (comp (ref "R57")
      (value "5.1k")
      (footprint "eagle-import:R0402")
      (libsource (lib "eagle-import") (part "R-US_R0402"))
    )
    (comp (ref "R59")
      (value "5.1k")
      (footprint "eagle-import:R0402")
      (libsource (lib "eagle-import") (part "R-US_R0402"))
    )
    (comp (ref "R64")
      (value "24.9k")
      (footprint "eagle-import:R0402")
      (libsource (lib "eagle-import") (part "R-US_R0402"))
    )
    (comp (ref "R66")
      (value "1.0M")
      (footprint "eagle-import:R0402")
      (libsource (lib "eagle-import") (part "R-US_R0402"))
    )
    (comp (ref "R71")
      (value "1.0M")
      (footprint "eagle-import:R0402")
      (libsource (lib "eagle-import") (part "R-US_R0402"))
    )
    (comp (ref "R74")
      (value "1.0M")
      (footprint "eagle-import:R0402")
      (libsource (lib "eagle-import") (part "R-US_R0402"))
    )
    (comp (ref "R80")
      (value "24.9k")
      (footprint "eagle-import:R0402")
      (libsource (lib "eagle-import") (part "R-US_R0402"))
    )
    (comp (ref "R86")
      (value "1.0M")
      (footprint "eagle-import:R0402")
      (libsource (lib "eagle-import") (part "R-US_R0402"))
    )
    (comp (ref "R87")
      (value "1.0M")
      (footprint "eagle-import:R0402")
      (libsource (lib "eagle-import") (part "R-US_R0402"))
    )
    (comp (ref "R91")
      (value "1.2k")
      (footprint "eagle-import:R0402")
      (libsource (lib "eagle-import") (part "R-US_R0402"))
    )
    (comp (ref "R96")
      (value "510")
      (footprint "eagle-import:R0603")
      (libsource (lib "eagle-import") (part "R-US_R0603"))
    )
    (comp (ref "R101")
      (value "20kB")
      (footprint "eagle-import:BOURNS_SLIDER")
      (libsource (lib "eagle-import") (part "BOURNS_SLIDER"))
    )
    (comp (ref "R104")
      (value "50kB")
      (footprint "eagle-import:ALPS_POT_NARROW")
      (libsource (lib "eagle-import") (part "POT_USVERTICAL_NARROW"))
    )
    (comp (ref "R109")
      (value "10kB")
      (footprint "eagle-import:ALPS_POT_NARROW")
      (libsource (lib "eagle-import") (part "POT_USVERTICAL_NARROW"))
    )
  )
  (nets
    (net (code "1") (name "1_TO_2") (class "Default")
      (node (ref "IC3") (pin "1") (pinfunction "OUT_1") (pintype "output"))
      (node (ref "R23") (pin "1") (pinfunction "1_1") (pintype "passive"))
      (node (ref "R58") (pin "2") (pinfunction "2_2") (pintype "passive"))
    )
    (net (code "2") (name "2_TO_3") (class "Default")
      (node (ref "IC7") (pin "8") (pinfunction "OUT_8") (pintype "output"))
      (node (ref "R30") (pin "2") (pinfunction "2_2") (pintype "passive"))
      (node (ref "R56") (pin "1") (pinfunction "1_1") (pintype "passive"))
    )
    (net (code "3") (name "3_TO_4") (class "Default")
      (node (ref "IC2") (pin "1") (pinfunction "OUT_1") (pintype "output"))
      (node (ref "R22") (pin "1") (pinfunction "1_1") (pintype "passive"))
      (node (ref "R57") (pin "2") (pinfunction "2_2") (pintype "passive"))
    )
    (net (code "4") (name "AREF_+10") (class "Default")
      (node (ref "C42") (pin "1") (pinfunction "1_1") (pintype "passive"))
      (node (ref "IC8") (pin "1") (pinfunction "C_1") (pintype "passive"))
      (node (ref "R102") (pin "P$1") (pinfunction "E_P$1") (pintype "passive"))
      (node (ref "R103") (pin "P$1") (pinfunction "E_P$1") (pintype "passive"))
      (node (ref "R104") (pin "P$1") (pinfunction "E_P$1") (pintype "passive"))
      (node (ref "R105") (pin "P$1") (pinfunction "E_P$1") (pintype "passive"))
      (node (ref "R61") (pin "2") (pinfunction "2_2") (pintype "passive"))
      (node (ref "R62") (pin "2") (pinfunction "2_2") (pintype "passive"))
      (node (ref "R63") (pin "2") (pinfunction "2_2") (pintype "passive"))
      (node (ref "R64") (pin "2") (pinfunction "2_2") (pintype "passive"))
      (node (ref "R69") (pin "2") (pinfunction "2_2") (pintype "passive"))
    )
    (net (code "5") (name "AREF_-2.5") (class "Default")
      (node (ref "C1") (pin "1") (pinfunction "1_1") (pintype "passive"))
      (node (ref "IC1") (pin "2") (pinfunction "A_2") (pintype "passive"))
      (node (ref "R18") (pin "2") (pinfunction "2_2") (pintype "passive"))
      (node (ref "R19") (pin "2") (pinfunction "2_2") (pintype "passive"))
      (node (ref "R20") (pin "2") (pinfunction "2_2") (pintype "passive"))
      (node (ref "R21") (pin "2") (pinfunction "2_2") (pintype "passive"))
      (node (ref "R35") (pin "2") (pinfunction "2_2") (pintype "passive"))
      (node (ref "R36") (pin "2") (pinfunction "2_2") (pintype "passive"))
      (node (ref "R45") (pin "2") (pinfunction "2_2") (pintype "passive"))
      (node (ref "R46") (pin "2") (pinfunction "2_2") (pintype "passive"))
      (node (ref "R5") (pin "2") (pinfunction "2_2") (pintype "passive"))
      (node (ref "R74") (pin "1") (pinfunction "1_1") (pintype "passive"))
      (node (ref "R75") (pin "1") (pinfunction "1_1") (pintype "passive"))
      (node (ref "R76") (pin "1") (pinfunction "1_1") (pintype "passive"))
      (node (ref "R77") (pin "1") (pinfunction "1_1") (pintype "passive"))
    )
    (net (code "6") (name "GND") (class "Default")
      (node (ref "C1") (pin "2") (pinfunction "2_2") (pintype "passive"))
      (node (ref "C10") (pin "2") (pinfunction "2_2") (pintype "passive"))
      (node (ref "C11") (pin "2") (pinfunction "2_2") (pintype "passive"))
      (node (ref "C12") (pin "1") (pinfunction "1_1") (pintype "passive"))
      (node (ref "C13") (pin "1") (pinfunction "1_1") (pintype "passive"))
      (node (ref "C18") (pin "2") (pinfunction "2_2") (pintype "passive"))
      (node (ref "C19") (pin "2") (pinfunction "2_2") (pintype "passive"))
      (node (ref "C2") (pin "2") (pinfunction "2_2") (pintype "passive"))
      (node (ref "C20") (pin "2") (pinfunction "2_2") (pintype "passive"))
      (node (ref "C21") (pin "2") (pinfunction "2_2") (pintype "passive"))
      (node (ref "C22") (pin "2") (pinfunction "2_2") (pintype "passive"))
      (node (ref "C23") (pin "2") (pinfunction "2_2") (pintype "passive"))
      (node (ref "C24") (pin "2") (pinfunction "2_2") (pintype "passive"))
      (node (ref "C25") (pin "2") (pinfunction "2_2") (pintype "passive"))
      (node (ref "C26") (pin "1") (pinfunction "1_1") (pintype "passive"))
      (node (ref "C27") (pin "2") (pinfunction "2_2") (pintype "passive"))
      (node (ref "C28") (pin "2") (pinfunction "2_2") (pintype "passive"))
      (node (ref "C29") (pin "1") (pinfunction "1_1") (pintype "passive"))
      (node (ref "C3") (pin "2") (pinfunction "2_2") (pintype "passive"))
      (node (ref "C34") (pin "2") (pinfunction "2_2") (pintype "passive"))
      (node (ref "C35") (pin "2") (pinfunction "2_2") (pintype "passive"))
      (node (ref "C36") (pin "2") (pinfunction "2_2") (pintype "passive"))
      (node (ref "C37") (pin "2") (pinfunction "2_2") (pintype "passive"))
      (node (ref "C38") (pin "1") (pinfunction "1_1") (pintype "passive"))
      (node (ref "C39") (pin "1") (pinfunction "1_1") (pintype "passive"))
      (node (ref "C4") (pin "2") (pinfunction "2_2") (pintype "passive"))
      (node (ref "C42") (pin "2") (pinfunction "2_2") (pintype "passive"))
      (node (ref "C43") (pin "2") (pinfunction "2_2") (pintype "passive"))
      (node (ref "C44") (pin "1") (pinfunction "1_1") (pintype "passive"))
      (node (ref "C45") (pin "2") (pinfunction "2_2") (pintype "passive"))
      (node (ref "C46") (pin "1") (pinfunction "1_1") (pintype "passive"))
      (node (ref "C47") (pin "1") (pinfunction "1_1") (pintype "passive"))
      (node (ref "C48") (pin "2") (pinfunction "2_2") (pintype "passive"))
      (node (ref "C49") (pin "1") (pinfunction "1_1") (pintype "passive"))
      (node (ref "C5") (pin "2") (pinfunction "2_2") (pintype "passive"))
      (node (ref "C50") (pin "2") (pinfunction "2_2") (pintype "passive"))
      (node (ref "C6") (pin "1") (pinfunction "1_1") (pintype "passive"))
      (node (ref "C7") (pin "1") (pinfunction "1_1") (pintype "passive"))
      (node (ref "D1") (pin "C") (pinfunction "C_C") (pintype "passive"))
      (node (ref "IC1") (pin "1") (pinfunction "C_1") (pintype "passive"))
      (node (ref "IC10") (pin "10") (pinfunction "+IN_10") (pintype "input"))
      (node (ref "IC10") (pin "12") (pinfunction "+IN_12") (pintype "input"))
      (node (ref "IC2") (pin "10") (pinfunction "+IN_10") (pintype "input"))
      (node (ref "IC2") (pin "12") (pinfunction "+IN_12") (pintype "input"))
      (node (ref "IC2") (pin "3") (pinfunction "+IN_3") (pintype "input"))
      (node (ref "IC2") (pin "5") (pinfunction "+IN_5") (pintype "input"))
      (node (ref "IC3") (pin "10") (pinfunction "+IN_10") (pintype "input"))
      (node (ref "IC3") (pin "12") (pinfunction "+IN_12") (pintype "input"))
      (node (ref "IC3") (pin "3") (pinfunction "+IN_3") (pintype "input"))
      (node (ref "IC3") (pin "5") (pinfunction "+IN_5") (pintype "input"))
      (node (ref "IC4") (pin "8") (pinfunction "GND_8") (pintype "power_in"))
      (node (ref "IC5") (pin "8") (pinfunction "GND_8") (pintype "power_in"))
      (node (ref "IC6") (pin "10") (pinfunction "+IN_10") (pintype "input"))
      (node (ref "IC6") (pin "12") (pinfunction "+IN_12") (pintype "input"))
      (node (ref "IC6") (pin "3") (pinfunction "+IN_3") (pintype "input"))
      (node (ref "IC6") (pin "5") (pinfunction "+IN_5") (pintype "input"))
      (node (ref "IC7") (pin "10") (pinfunction "+IN_10") (pintype "input"))
      (node (ref "IC7") (pin "12") (pinfunction "+IN_12") (pintype "input"))
      (node (ref "IC7") (pin "3") (pinfunction "+IN_3") (pintype "input"))
      (node (ref "IC7") (pin "5") (pinfunction "+IN_5") (pintype "input"))
      (node (ref "IC8") (pin "2") (pinfunction "A_2") (pintype "passive"))
      (node (ref "IC9") (pin "10") (pinfunction "+IN_10") (pintype "input"))
      (node (ref "IC9") (pin "12") (pinfunction "+IN_12") (pintype "input"))
      (node (ref "J1") (pin "P1") (pinfunction "1_P1") (pintype "passive"))
      (node (ref "J10") (pin "P1") (pinfunction "1_P1") (pintype "passive"))
      (node (ref "J11") (pin "P1") (pinfunction "1_P1") (pintype "passive"))
      (node (ref "J12") (pin "P1") (pinfunction "1_P1") (pintype "passive"))
      (node (ref "J2") (pin "P1") (pinfunction "1_P1") (pintype "passive"))
      (node (ref "J3") (pin "P1") (pinfunction "1_P1") (pintype "passive"))
      (node (ref "J4") (pin "P1") (pinfunction "1_P1") (pintype "passive"))
      (node (ref "J5") (pin "P1") (pinfunction "1_P1") (pintype "passive"))
      (node (ref "J5") (pin "P2") (pinfunction "2_P2") (pintype "passive"))
      (node (ref "J6") (pin "P1") (pinfunction "1_P1") (pintype "passive"))
      (node (ref "J6") (pin "P2") (pinfunction "2_P2") (pintype "passive"))
      (node (ref "J7") (pin "P1") (pinfunction "1_P1") (pintype "passive"))
      (node (ref "J7") (pin "P2") (pinfunction "2_P2") (pintype "passive"))
      (node (ref "J8") (pin "P1") (pinfunction "1_P1") (pintype "passive"))
      (node (ref "J8") (pin "P2") (pinfunction "2_P2") (pintype "passive"))
      (node (ref "J9") (pin "P1") (pinfunction "1_P1") (pintype "passive"))
      (node (ref "JP1") (pin "3") (pinfunction "3_3") (pintype "passive"))
      (node (ref "JP1") (pin "4") (pinfunction "4_4") (pintype "passive"))
      (node (ref "JP1") (pin "5") (pinfunction "5_5") (pintype "passive"))
      (node (ref "JP1") (pin "6") (pinfunction "6_6") (pintype "passive"))
      (node (ref "JP1") (pin "7") (pinfunction "7_7") (pintype "passive"))
      (node (ref "JP1") (pin "8") (pinfunction "8_8") (pintype "passive"))
      (node (ref "R1") (pin "1") (pinfunction "1_1") (pintype "passive"))
      (node (ref "R10") (pin "2") (pinfunction "2_2") (pintype "passive"))
      (node (ref "R100") (pin "3") (pinfunction "E_3") (pintype "passive"))
      (node (ref "R101") (pin "3") (pinfunction "E_3") (pintype "passive"))
      (node (ref "R102") (pin "P$3") (pinfunction "A_P$3") (pintype "passive"))
      (node (ref "R103") (pin "P$3") (pinfunction "A_P$3") (pintype "passive"))
      (node (ref "R104") (pin "P$3") (pinfunction "A_P$3") (pintype "passive"))
      (node (ref "R105") (pin "P$3") (pinfunction "A_P$3") (pintype "passive"))
      (node (ref "R11") (pin "2") (pinfunction "2_2") (pintype "passive"))
      (node (ref "R12") (pin "2") (pinfunction "2_2") (pintype "passive"))
      (node (ref "R13") (pin "2") (pinfunction "2_2") (pintype "passive"))
      (node (ref "R2") (pin "1") (pinfunction "1_1") (pintype "passive"))
      (node (ref "R3") (pin "1") (pinfunction "1_1") (pintype "passive"))
      (node (ref "R4") (pin "1") (pinfunction "1_1") (pintype "passive"))
      (node (ref "R83") (pin "1") (pinfunction "1_1") (pintype "passive"))
      (node (ref "R84") (pin "1") (pinfunction "1_1") (pintype "passive"))
      (node (ref "R87") (pin "1") (pinfunction "1_1") (pintype "passive"))
      (node (ref "R88") (pin "1") (pinfunction "1_1") (pintype "passive"))
      (node (ref "R90") (pin "2") (pinfunction "2_2") (pintype "passive"))
      (node (ref "R91") (pin "2") (pinfunction "2_2") (pintype "passive"))
      (node (ref "R92") (pin "2") (pinfunction "2_2") (pintype "passive"))
      (node (ref "R93") (pin "2") (pinfunction "2_2") (pintype "passive"))
      (node (ref "R98") (pin "3") (pinfunction "E_3") (pintype "passive"))
      (node (ref "R99") (pin "3") (pinfunction "E_3") (pintype "passive"))
    )
    (net (code "7") (name "Net-(C20-Pad1)") (class "Default")
      (node (ref "C20") (pin "1") (pinfunction "1_1") (pintype "passive"))
      (node (ref "R39") (pin "1") (pinfunction "1_1") (pintype "passive"))
    )
    (net (code "8") (name "Net-(C21-Pad1)") (class "Default")
      (node (ref "C21") (pin "1") (pinfunction "1_1") (pintype "passive"))
      (node (ref "R40") (pin "1") (pinfunction "1_1") (pintype "passive"))
    )
    (net (code "9") (name "Net-(C22-Pad1)") (class "Default")
      (node (ref "C22") (pin "1") (pinfunction "1_1") (pintype "passive"))
      (node (ref "R41") (pin "1") (pinfunction "1_1") (pintype "passive"))
    )
    (net (code "10") (name "Net-(C23-Pad1)") (class "Default")
      (node (ref "C23") (pin "1") (pinfunction "1_1") (pintype "passive"))
      (node (ref "R42") (pin "1") (pinfunction "1_1") (pintype "passive"))
    )
    (net (code "11") (name "Net-(C24-Pad1)") (class "Default")
      (node (ref "C24") (pin "1") (pinfunction "1_1") (pintype "passive"))
      (node (ref "R43") (pin "1") (pinfunction "1_1") (pintype "passive"))
    )
    (net (code "12") (name "Net-(C25-Pad1)") (class "Default")
      (node (ref "C25") (pin "1") (pinfunction "1_1") (pintype "passive"))
      (node (ref "R44") (pin "1") (pinfunction "1_1") (pintype "passive"))
    )
    (net (code "13") (name "Net-(C27-Pad1)") (class "Default")
      (node (ref "C27") (pin "1") (pinfunction "1_1") (pintype "passive"))
      (node (ref "R49") (pin "1") (pinfunction "1_1") (pintype "passive"))
    )
    (net (code "14") (name "Net-(C28-Pad1)") (class "Default")
      (node (ref "C28") (pin "1") (pinfunction "1_1") (pintype "passive"))
      (node (ref "R50") (pin "1") (pinfunction "1_1") (pintype "passive"))
    )
    (net (code "15") (name "Net-(D2-PadA)") (class "Default")
      (node (ref "D2") (pin "A") (pinfunction "A_A") (pintype "passive"))
      (node (ref "JP1") (pin "1") (pinfunction "1_1") (pintype "passive"))
      (node (ref "JP1") (pin "2") (pinfunction "2_2") (pintype "passive"))
    )
    (net (code "16") (name "Net-(D2-PadC)") (class "Default")
      (node (ref "D2") (pin "C") (pinfunction "C_C") (pintype "passive"))
      (node (ref "L2") (pin "2") (pinfunction "2_2") (pintype "passive"))
    )
    (net (code "17") (name "Net-(IC2A--IN)") (class "Default")
      (node (ref "IC2") (pin "2") (pinfunction "-IN_2") (pintype "input"))
      (node (ref "R22") (pin "2") (pinfunction "2_2") (pintype "passive"))
      (node (ref "R24") (pin "1") (pinfunction "1_1") (pintype "passive"))
    )
    (net (code "18") (name "Net-(IC2B--IN)") (class "Default")
      (node (ref "C16") (pin "1") (pinfunction "1_1") (pintype "passive"))
      (node (ref "IC2") (pin "6") (pinfunction "-IN_6") (pintype "input"))
      (node (ref "IC4") (pin "13") (pinfunction "OUT_13") (pintype "output"))
      (node (ref "R31") (pin "2") (pinfunction "2_2") (pintype "passive"))
    )
    (net (code "19") (name "Net-(IC2B-OUT)") (class "Default")
      (node (ref "C16") (pin "2") (pinfunction "2_2") (pintype "passive"))
      (node (ref "IC2") (pin "7") (pinfunction "OUT_7") (pintype "output"))
      (node (ref "R26") (pin "2") (pinfunction "2_2") (pintype "passive"))
      (node (ref "R31") (pin "1") (pinfunction "1_1") (pintype "passive"))
    )
    (net (code "20") (name "Net-(IC2C--IN)") (class "Default")
      (node (ref "C14") (pin "1") (pinfunction "1_1") (pintype "passive"))
      (node (ref "IC2") (pin "9") (pinfunction "-IN_9") (pintype "input"))
      (node (ref "R26") (pin "1") (pinfunction "1_1") (pintype "passive"))
      (node (ref "R28") (pin "2") (pinfunction "2_2") (pintype "passive"))
      (node (ref "R30") (pin "1") (pinfunction "1_1") (pintype "passive"))
    )
    (net (code "21") (name "Net-(IC2C-OUT)") (class "Default")
      (node (ref "C14") (pin "2") (pinfunction "2_2") (pintype "passive"))
      (node (ref "IC2") (pin "8") (pinfunction "OUT_8") (pintype "output"))
      (node (ref "R28") (pin "1") (pinfunction "1_1") (pintype "passive"))
      (node (ref "R89") (pin "1") (pinfunction "1_1") (pintype "passive"))
      (node (ref "R94") (pin "2") (pinfunction "2_2") (pintype "passive"))
    )
    (net (code "22") (name "Net-(IC2D--IN)") (class "Default")
      (node (ref "C8") (pin "1") (pinfunction "1_1") (pintype "passive"))
      (node (ref "IC2") (pin "13") (pinfunction "-IN_13") (pintype "input"))
      (node (ref "IC4") (pin "4") (pinfunction "OUT_4") (pintype "output"))
      (node (ref "R100") (pin "1") (pinfunction "A_1") (pintype "passive"))
      (node (ref "R16") (pin "1") (pinfunction "1_1") (pintype "passive"))
      (node (ref "R19") (pin "1") (pinfunction "1_1") (pintype "passive"))
    )
    (net (code "23") (name "Net-(IC2D-OUT)") (class "Default")
      (node (ref "C8") (pin "2") (pinfunction "2_2") (pintype "passive"))
      (node (ref "IC2") (pin "14") (pinfunction "OUT_14") (pintype "output"))
      (node (ref "IC4") (pin "14") (pinfunction "CTRL_14") (pintype "input"))
      (node (ref "R108") (pin "P$1") (pinfunction "E_P$1") (pintype "passive"))
      (node (ref "R65") (pin "1") (pinfunction "1_1") (pintype "passive"))
    )
    (net (code "24") (name "Net-(IC3A--IN)") (class "Default")
      (node (ref "IC3") (pin "2") (pinfunction "-IN_2") (pintype "input"))
      (node (ref "R23") (pin "2") (pinfunction "2_2") (pintype "passive"))
      (node (ref "R25") (pin "1") (pinfunction "1_1") (pintype "passive"))
    )
    (net (code "25") (name "Net-(IC3B--IN)") (class "Default")
      (node (ref "C17") (pin "1") (pinfunction "1_1") (pintype "passive"))
      (node (ref "IC3") (pin "6") (pinfunction "-IN_6") (pintype "input"))
      (node (ref "IC5") (pin "13") (pinfunction "OUT_13") (pintype "output"))
      (node (ref "R32") (pin "2") (pinfunction "2_2") (pintype "passive"))
    )
    (net (code "26") (name "Net-(IC3B-OUT)") (class "Default")
      (node (ref "C17") (pin "2") (pinfunction "2_2") (pintype "passive"))
      (node (ref "IC3") (pin "7") (pinfunction "OUT_7") (pintype "output"))
      (node (ref "R27") (pin "2") (pinfunction "2_2") (pintype "passive"))
      (node (ref "R32") (pin "1") (pinfunction "1_1") (pintype "passive"))
    )
    (net (code "27") (name "Net-(IC3C--IN)") (class "Default")
      (node (ref "C15") (pin "1") (pinfunction "1_1") (pintype "passive"))
      (node (ref "IC3") (pin "9") (pinfunction "-IN_9") (pintype "input"))
      (node (ref "R27") (pin "1") (pinfunction "1_1") (pintype "passive"))
      (node (ref "R29") (pin "2") (pinfunction "2_2") (pintype "passive"))
    )
    (net (code "28") (name "Net-(IC3C-OUT)") (class "Default")
      (node (ref "C15") (pin "2") (pinfunction "2_2") (pintype "passive"))
      (node (ref "IC3") (pin "8") (pinfunction "OUT_8") (pintype "output"))
      (node (ref "R29") (pin "1") (pinfunction "1_1") (pintype "passive"))
      (node (ref "R85") (pin "1") (pinfunction "1_1") (pintype "passive"))
      (node (ref "R95") (pin "2") (pinfunction "2_2") (pintype "passive"))
    )
    (net (code "29") (name "Net-(IC3D--IN)") (class "Default")
      (node (ref "C9") (pin "1") (pinfunction "1_1") (pintype "passive"))
      (node (ref "IC3") (pin "13") (pinfunction "-IN_13") (pintype "input"))
      (node (ref "IC5") (pin "4") (pinfunction "OUT_4") (pintype "output"))
      (node (ref "R15") (pin "1") (pinfunction "1_1") (pintype "passive"))
      (node (ref "R21") (pin "1") (pinfunction "1_1") (pintype "passive"))
      (node (ref "R98") (pin "1") (pinfunction "A_1") (pintype "passive"))
    )
    (net (code "30") (name "Net-(IC3D-OUT)") (class "Default")
      (node (ref "C9") (pin "2") (pinfunction "2_2") (pintype "passive"))
      (node (ref "IC3") (pin "14") (pinfunction "OUT_14") (pintype "output"))
      (node (ref "IC5") (pin "14") (pinfunction "CTRL_14") (pintype "input"))
      (node (ref "R106") (pin "P$1") (pinfunction "E_P$1") (pintype "passive"))
      (node (ref "R68") (pin "1") (pinfunction "1_1") (pintype "passive"))
    )
    (net (code "31") (name "Net-(IC4A-CTRL)") (class "Default")
      (node (ref "IC4") (pin "3") (pinfunction "CTRL_3") (pintype "input"))
      (node (ref "R108") (pin "P$2") (pinfunction "S_P$2") (pintype "passive"))
    )
    (net (code "32") (name "Net-(IC4A-IN)") (class "Default")
      (node (ref "IC4") (pin "2") (pinfunction "IN_2") (pintype "input"))
      (node (ref "R35") (pin "1") (pinfunction "1_1") (pintype "passive"))
      (node (ref "R39") (pin "2") (pinfunction "2_2") (pintype "passive"))
    )
    (net (code "33") (name "Net-(IC4B-CTRL)") (class "Default")
      (node (ref "IC4") (pin "6") (pinfunction "CTRL_6") (pintype "input"))
      (node (ref "R109") (pin "P$2") (pinfunction "S_P$2") (pintype "passive"))
    )
    (net (code "34") (name "Net-(IC4B-IN)") (class "Default")
      (node (ref "IC4") (pin "7") (pinfunction "IN_7") (pintype "input"))
      (node (ref "R46") (pin "1") (pinfunction "1_1") (pintype "passive"))
      (node (ref "R50") (pin "2") (pinfunction "2_2") (pintype "passive"))
    )
    (net (code "35") (name "Net-(IC4B-OUT)") (class "Default")
      (node (ref "C30") (pin "1") (pinfunction "1_1") (pintype "passive"))
      (node (ref "IC4") (pin "5") (pinfunction "OUT_5") (pintype "output"))
      (node (ref "IC6") (pin "2") (pinfunction "-IN_2") (pintype "input"))
      (node (ref "R101") (pin "1") (pinfunction "A_1") (pintype "passive"))
      (node (ref "R17") (pin "1") (pinfunction "1_1") (pintype "passive"))
      (node (ref "R18") (pin "1") (pinfunction "1_1") (pintype "passive"))
    )
    (net (code "36") (name "Net-(IC4C-CTRL)") (class "Default")
      (node (ref "C30") (pin "2") (pinfunction "2_2") (pintype "passive"))
      (node (ref "IC4") (pin "11") (pinfunction "CTRL_11") (pintype "input"))
      (node (ref "IC6") (pin "1") (pinfunction "OUT_1") (pintype "output"))
      (node (ref "R109") (pin "P$1") (pinfunction "E_P$1") (pintype "passive"))
      (node (ref "R66") (pin "1") (pinfunction "1_1") (pintype "passive"))
    )
    (net (code "37") (name "Net-(IC4C-IN)") (class "Default")
      (node (ref "IC4") (pin "10") (pinfunction "IN_10") (pintype "input"))
      (node (ref "R43") (pin "2") (pinfunction "2_2") (pintype "passive"))
      (node (ref "R47") (pin "1") (pinfunction "1_1") (pintype "passive"))
    )
    (net (code "38") (name "Net-(IC4C-OUT)") (class "Default")
      (node (ref "C32") (pin "1") (pinfunction "1_1") (pintype "passive"))
      (node (ref "IC4") (pin "12") (pinfunction "OUT_12") (pintype "output"))
      (node (ref "IC6") (pin "13") (pinfunction "-IN_13") (pintype "input"))
      (node (ref "R51") (pin "2") (pinfunction "2_2") (pintype "passive"))
    )
    (net (code "39") (name "Net-(IC4D-IN)") (class "Default")
      (node (ref "IC4") (pin "15") (pinfunction "IN_15") (pintype "input"))
      (node (ref "R37") (pin "1") (pinfunction "1_1") (pintype "passive"))
      (node (ref "R41") (pin "2") (pinfunction "2_2") (pintype "passive"))
    )
    (net (code "40") (name "Net-(IC4E-MODE)") (class "Default")
      (node (ref "IC4") (pin "1") (pinfunction "MODE_1") (pintype "input"))
      (node (ref "R34") (pin "2") (pinfunction "2_2") (pintype "passive"))
    )
    (net (code "41") (name "Net-(IC5A-CTRL)") (class "Default")
      (node (ref "IC5") (pin "3") (pinfunction "CTRL_3") (pintype "input"))
      (node (ref "R106") (pin "P$2") (pinfunction "S_P$2") (pintype "passive"))
    )
    (net (code "42") (name "Net-(IC5A-IN)") (class "Default")
      (node (ref "IC5") (pin "2") (pinfunction "IN_2") (pintype "input"))
      (node (ref "R36") (pin "1") (pinfunction "1_1") (pintype "passive"))
      (node (ref "R40") (pin "2") (pinfunction "2_2") (pintype "passive"))
    )
    (net (code "43") (name "Net-(IC5B-CTRL)") (class "Default")
      (node (ref "IC5") (pin "6") (pinfunction "CTRL_6") (pintype "input"))
      (node (ref "R107") (pin "P$2") (pinfunction "S_P$2") (pintype "passive"))
    )
    (net (code "44") (name "Net-(IC5B-IN)") (class "Default")
      (node (ref "IC5") (pin "7") (pinfunction "IN_7") (pintype "input"))
      (node (ref "R45") (pin "1") (pinfunction "1_1") (pintype "passive"))
      (node (ref "R49") (pin "2") (pinfunction "2_2") (pintype "passive"))
    )
    (net (code "45") (name "Net-(IC5B-OUT)") (class "Default")
      (node (ref "C33") (pin "1") (pinfunction "1_1") (pintype "passive"))
      (node (ref "IC5") (pin "5") (pinfunction "OUT_5") (pintype "output"))
      (node (ref "IC7") (pin "2") (pinfunction "-IN_2") (pintype "input"))
      (node (ref "R14") (pin "1") (pinfunction "1_1") (pintype "passive"))
      (node (ref "R20") (pin "1") (pinfunction "1_1") (pintype "passive"))
      (node (ref "R99") (pin "1") (pinfunction "A_1") (pintype "passive"))
    )
    (net (code "46") (name "Net-(IC5C-CTRL)") (class "Default")
      (node (ref "C33") (pin "2") (pinfunction "2_2") (pintype "passive"))
      (node (ref "IC5") (pin "11") (pinfunction "CTRL_11") (pintype "input"))
      (node (ref "IC7") (pin "1") (pinfunction "OUT_1") (pintype "output"))
      (node (ref "R107") (pin "P$1") (pinfunction "E_P$1") (pintype "passive"))
      (node (ref "R67") (pin "1") (pinfunction "1_1") (pintype "passive"))
    )
    (net (code "47") (name "Net-(IC5C-IN)") (class "Default")
      (node (ref "IC5") (pin "10") (pinfunction "IN_10") (pintype "input"))
      (node (ref "R44") (pin "2") (pinfunction "2_2") (pintype "passive"))
      (node (ref "R48") (pin "1") (pinfunction "1_1") (pintype "passive"))
    )
    (net (code "48") (name "Net-(IC5C-OUT)") (class "Default")
      (node (ref "C31") (pin "1") (pinfunction "1_1") (pintype "passive"))
      (node (ref "IC5") (pin "12") (pinfunction "OUT_12") (pintype "output"))
      (node (ref "IC7") (pin "13") (pinfunction "-IN_13") (pintype "input"))
      (node (ref "R52") (pin "2") (pinfunction "2_2") (pintype "passive"))
    )
    (net (code "49") (name "Net-(IC5D-IN)") (class "Default")
      (node (ref "IC5") (pin "15") (pinfunction "IN_15") (pintype "input"))
      (node (ref "R38") (pin "1") (pinfunction "1_1") (pintype "passive"))
      (node (ref "R42") (pin "2") (pinfunction "2_2") (pintype "passive"))
    )
    (net (code "50") (name "Net-(IC5E-MODE)") (class "Default")
      (node (ref "IC5") (pin "1") (pinfunction "MODE_1") (pintype "input"))
      (node (ref "R33") (pin "2") (pinfunction "2_2") (pintype "passive"))
    )
    (net (code "51") (name "Net-(IC6B--IN)") (class "Default")
      (node (ref "C41") (pin "1") (pinfunction "1_1") (pintype "passive"))
      (node (ref "IC6") (pin "6") (pinfunction "-IN_6") (pintype "input"))
      (node (ref "R53") (pin "1") (pinfunction "1_1") (pintype "passive"))
      (node (ref "R57") (pin "1") (pinfunction "1_1") (pintype "passive"))
      (node (ref "R59") (pin "2") (pinfunction "2_2") (pintype "passive"))
    )
    (net (code "52") (name "Net-(IC6B-OUT)") (class "Default")
      (node (ref "C41") (pin "2") (pinfunction "2_2") (pintype "passive"))
      (node (ref "IC6") (pin "7") (pinfunction "OUT_7") (pintype "output"))
      (node (ref "R59") (pin "1") (pinfunction "1_1") (pintype "passive"))
      (node (ref "R86") (pin "1") (pinfunction "1_1") (pintype "passive"))
      (node (ref "R96") (pin "2") (pinfunction "2_2") (pintype "passive"))
    )
    (net (code "53") (name "Net-(IC6C--IN)") (class "Default")
      (node (ref "IC6") (pin "8") (pinfunction "OUT_8") (pintype "output"))
      (node (ref "IC6") (pin "9") (pinfunction "-IN_9") (pintype "input"))
    )
    (net (code "54") (name "Net-(IC6D-OUT)") (class "Default")
      (node (ref "C32") (pin "2") (pinfunction "2_2") (pintype "passive"))
      (node (ref "IC6") (pin "14") (pinfunction "OUT_14") (pintype "output"))
      (node (ref "R51") (pin "1") (pinfunction "1_1") (pintype "passive"))
      (node (ref "R53") (pin "2") (pinfunction "2_2") (pintype "passive"))
    )
    (net (code "55") (name "Net-(IC7B--IN)") (class "Default")
      (node (ref "C40") (pin "1") (pinfunction "1_1") (pintype "passive"))
      (node (ref "IC7") (pin "6") (pinfunction "-IN_6") (pintype "input"))
      (node (ref "R54") (pin "1") (pinfunction "1_1") (pintype "passive"))
      (node (ref "R58") (pin "1") (pinfunction "1_1") (pintype "passive"))
      (node (ref "R60") (pin "2") (pinfunction "2_2") (pintype "passive"))
    )
    (net (code "56") (name "Net-(IC7B-OUT)") (class "Default")
      (node (ref "C40") (pin "2") (pinfunction "2_2") (pintype "passive"))
      (node (ref "IC7") (pin "7") (pinfunction "OUT_7") (pintype "output"))
      (node (ref "R60") (pin "1") (pinfunction "1_1") (pintype "passive"))
      (node (ref "R82") (pin "1") (pinfunction "1_1") (pintype "passive"))
      (node (ref "R97") (pin "2") (pinfunction "2_2") (pintype "passive"))
    )
    (net (code "57") (name "Net-(IC7C--IN)") (class "Default")
      (node (ref "IC7") (pin "9") (pinfunction "-IN_9") (pintype "input"))
      (node (ref "R55") (pin "1") (pinfunction "1_1") (pintype "passive"))
      (node (ref "R56") (pin "2") (pinfunction "2_2") (pintype "passive"))
    )
    (net (code "58") (name "Net-(IC7D-OUT)") (class "Default")
      (node (ref "C31") (pin "2") (pinfunction "2_2") (pintype "passive"))
      (node (ref "IC7") (pin "14") (pinfunction "OUT_14") (pintype "output"))
      (node (ref "R52") (pin "1") (pinfunction "1_1") (pintype "passive"))
      (node (ref "R54") (pin "2") (pinfunction "2_2") (pintype "passive"))
    )
    (net (code "59") (name "Net-(IC9A-+IN)") (class "Default")
      (node (ref "IC9") (pin "3") (pinfunction "+IN_3") (pintype "input"))
      (node (ref "R86") (pin "2") (pinfunction "2_2") (pintype "passive"))
      (node (ref "R87") (pin "2") (pinfunction "2_2") (pintype "passive"))
    )
    (net (code "60") (name "Net-(IC9A--IN)") (class "Default")
      (node (ref "IC9") (pin "2") (pinfunction "-IN_2") (pintype "input"))
      (node (ref "LED4") (pin "A") (pinfunction "A_A") (pintype "passive"))
      (node (ref "R91") (pin "1") (pinfunction "1_1") (pintype "passive"))
    )
    (net (code "61") (name "Net-(IC9A-OUT)") (class "Default")
      (node (ref "IC9") (pin "1") (pinfunction "OUT_1") (pintype "output"))
      (node (ref "LED4") (pin "K") (pinfunction "C_K") (pintype "passive"))
    )
    (net (code "62") (name "Net-(IC9B-+IN)") (class "Default")
      (node (ref "IC9") (pin "5") (pinfunction "+IN_5") (pintype "input"))
      (node (ref "R88") (pin "2") (pinfunction "2_2") (pintype "passive"))
      (node (ref "R89") (pin "2") (pinfunction "2_2") (pintype "passive"))
    )
    (net (code "63") (name "Net-(IC9B--IN)") (class "Default")
      (node (ref "IC9") (pin "6") (pinfunction "-IN_6") (pintype "input"))
      (node (ref "LED3") (pin "A") (pinfunction "A_A") (pintype "passive"))
      (node (ref "R92") (pin "1") (pinfunction "1_1") (pintype "passive"))
    )
    (net (code "64") (name "Net-(IC9B-OUT)") (class "Default")
      (node (ref "IC9") (pin "7") (pinfunction "OUT_7") (pintype "output"))
      (node (ref "LED3") (pin "K") (pinfunction "C_K") (pintype "passive"))
    )
    (net (code "65") (name "Net-(IC9C--IN)") (class "Default")
      (node (ref "IC9") (pin "9") (pinfunction "-IN_9") (pintype "input"))
      (node (ref "R65") (pin "2") (pinfunction "2_2") (pintype "passive"))
      (node (ref "R70") (pin "1") (pinfunction "1_1") (pintype "passive"))
      (node (ref "R75") (pin "2") (pinfunction "2_2") (pintype "passive"))
    )
    (net (code "66") (name "Net-(IC9C-OUT)") (class "Default")
      (node (ref "IC9") (pin "8") (pinfunction "OUT_8") (pintype "output"))
      (node (ref "R78") (pin "1") (pinfunction "1_1") (pintype "passive"))
    )
    (net (code "67") (name "Net-(IC9D--IN)") (class "Default")
      (node (ref "IC9") (pin "13") (pinfunction "-IN_13") (pintype "input"))
      (node (ref "R66") (pin "2") (pinfunction "2_2") (pintype "passive"))
      (node (ref "R71") (pin "1") (pinfunction "1_1") (pintype "passive"))
      (node (ref "R74") (pin "2") (pinfunction "2_2") (pintype "passive"))
    )
    (net (code "68") (name "Net-(IC9D-OUT)") (class "Default")
      (node (ref "IC9") (pin "14") (pinfunction "OUT_14") (pintype "output"))
      (node (ref "R80") (pin "1") (pinfunction "1_1") (pintype "passive"))
    )
    (net (code "69") (name "Net-(IC10A-+IN)") (class "Default")
      (node (ref "IC10") (pin "3") (pinfunction "+IN_3") (pintype "input"))
      (node (ref "R82") (pin "2") (pinfunction "2_2") (pintype "passive"))
      (node (ref "R83") (pin "2") (pinfunction "2_2") (pintype "passive"))
    )
    (net (code "70") (name "Net-(IC10A--IN)") (class "Default")
      (node (ref "IC10") (pin "2") (pinfunction "-IN_2") (pintype "input"))
      (node (ref "LED2") (pin "A") (pinfunction "A_A") (pintype "passive"))
      (node (ref "R93") (pin "1") (pinfunction "1_1") (pintype "passive"))
    )
    (net (code "71") (name "Net-(IC10A-OUT)") (class "Default")
      (node (ref "IC10") (pin "1") (pinfunction "OUT_1") (pintype "output"))
      (node (ref "LED2") (pin "K") (pinfunction "C_K") (pintype "passive"))
    )
    (net (code "72") (name "Net-(IC10B-+IN)") (class "Default")
      (node (ref "IC10") (pin "5") (pinfunction "+IN_5") (pintype "input"))
      (node (ref "R84") (pin "2") (pinfunction "2_2") (pintype "passive"))
      (node (ref "R85") (pin "2") (pinfunction "2_2") (pintype "passive"))
    )
    (net (code "73") (name "Net-(IC10B--IN)") (class "Default")
      (node (ref "IC10") (pin "6") (pinfunction "-IN_6") (pintype "input"))
      (node (ref "LED1") (pin "A") (pinfunction "A_A") (pintype "passive"))
      (node (ref "R90") (pin "1") (pinfunction "1_1") (pintype "passive"))
    )
    (net (code "74") (name "Net-(IC10B-OUT)") (class "Default")
      (node (ref "IC10") (pin "7") (pinfunction "OUT_7") (pintype "output"))
      (node (ref "LED1") (pin "K") (pinfunction "C_K") (pintype "passive"))
    )
    (net (code "75") (name "Net-(IC10C--IN)") (class "Default")
      (node (ref "IC10") (pin "9") (pinfunction "-IN_9") (pintype "input"))
      (node (ref "R68") (pin "2") (pinfunction "2_2") (pintype "passive"))
      (node (ref "R73") (pin "1") (pinfunction "1_1") (pintype "passive"))
      (node (ref "R77") (pin "2") (pinfunction "2_2") (pintype "passive"))
    )
    (net (code "76") (name "Net-(IC10C-OUT)") (class "Default")
      (node (ref "IC10") (pin "8") (pinfunction "OUT_8") (pintype "output"))
      (node (ref "R81") (pin "1") (pinfunction "1_1") (pintype "passive"))
    )
    (net (code "77") (name "Net-(IC10D--IN)") (class "Default")
      (node (ref "IC10") (pin "13") (pinfunction "-IN_13") (pintype "input"))
      (node (ref "R67") (pin "2") (pinfunction "2_2") (pintype "passive"))
      (node (ref "R72") (pin "1") (pinfunction "1_1") (pintype "passive"))
      (node (ref "R76") (pin "2") (pinfunction "2_2") (pintype "passive"))
    )
    (net (code "78") (name "Net-(IC10D-OUT)") (class "Default")
      (node (ref "IC10") (pin "14") (pinfunction "OUT_14") (pintype "output"))
      (node (ref "R79") (pin "1") (pinfunction "1_1") (pintype "passive"))
    )
    (net (code "79") (name "Net-(J1-2)") (class "Default")
      (node (ref "J1") (pin "P2") (pinfunction "2_P2") (pintype "passive"))
      (node (ref "R25") (pin "2") (pinfunction "2_2") (pintype "passive"))
    )
    (net (code "80") (name "Net-(J1-3)") (class "Default")
      (node (ref "J1") (pin "P3") (pinfunction "3_P3") (pintype "passive"))
      (node (ref "R95") (pin "1") (pinfunction "1_1") (pintype "passive"))
    )
    (net (code "81") (name "Net-(J2-2)") (class "Default")
      (node (ref "J2") (pin "P2") (pinfunction "2_P2") (pintype "passive"))
      (node (ref "R55") (pin "2") (pinfunction "2_2") (pintype "passive"))
    )
    (net (code "82") (name "Net-(J2-3)") (class "Default")
      (node (ref "J2") (pin "P3") (pinfunction "3_P3") (pintype "passive"))
      (node (ref "R97") (pin "1") (pinfunction "1_1") (pintype "passive"))
    )
    (net (code "83") (name "Net-(J3-2)") (class "Default")
      (node (ref "J3") (pin "P2") (pinfunction "2_P2") (pintype "passive"))
      (node (ref "R24") (pin "2") (pinfunction "2_2") (pintype "passive"))
    )
    (net (code "84") (name "Net-(J3-3)") (class "Default")
      (node (ref "J3") (pin "P3") (pinfunction "3_P3") (pintype "passive"))
      (node (ref "R94") (pin "1") (pinfunction "1_1") (pintype "passive"))
    )
    (net (code "85") (name "Net-(J4-3)") (class "Default")
      (node (ref "J4") (pin "P3") (pinfunction "3_P3") (pintype "passive"))
      (node (ref "R96") (pin "1") (pinfunction "1_1") (pintype "passive"))
    )
    (net (code "86") (name "Net-(J5-3)") (class "Default")
      (node (ref "J5") (pin "P3") (pinfunction "3_P3") (pintype "passive"))
      (node (ref "R38") (pin "2") (pinfunction "2_2") (pintype "passive"))
    )
    (net (code "87") (name "Net-(J6-3)") (class "Default")
      (node (ref "J6") (pin "P3") (pinfunction "3_P3") (pintype "passive"))
      (node (ref "R48") (pin "2") (pinfunction "2_2") (pintype "passive"))
    )
    (net (code "88") (name "Net-(J7-3)") (class "Default")
      (node (ref "J7") (pin "P3") (pinfunction "3_P3") (pintype "passive"))
      (node (ref "R37") (pin "2") (pinfunction "2_2") (pintype "passive"))
    )
    (net (code "89") (name "Net-(J8-3)") (class "Default")
      (node (ref "J8") (pin "P3") (pinfunction "3_P3") (pintype "passive"))
      (node (ref "R47") (pin "2") (pinfunction "2_2") (pintype "passive"))
    )
    (net (code "90") (name "Net-(J9-2)") (class "Default")
      (node (ref "J9") (pin "P2") (pinfunction "2_P2") (pintype "passive"))
      (node (ref "R61") (pin "1") (pinfunction "1_1") (pintype "passive"))
    )
    (net (code "91") (name "Net-(J9-3)") (class "Default")
      (node (ref "J9") (pin "P3") (pinfunction "3_P3") (pintype "passive"))
      (node (ref "R7") (pin "2") (pinfunction "2_2") (pintype "passive"))
    )
    (net (code "92") (name "Net-(J10-2)") (class "Default")
      (node (ref "J10") (pin "P2") (pinfunction "2_P2") (pintype "passive"))
      (node (ref "R63") (pin "1") (pinfunction "1_1") (pintype "passive"))
    )
    (net (code "93") (name "Net-(J10-3)") (class "Default")
      (node (ref "J10") (pin "P3") (pinfunction "3_P3") (pintype "passive"))
      (node (ref "R8") (pin "2") (pinfunction "2_2") (pintype "passive"))
    )
    (net (code "94") (name "Net-(J11-2)") (class "Default")
      (node (ref "J11") (pin "P2") (pinfunction "2_P2") (pintype "passive"))
      (node (ref "R62") (pin "1") (pinfunction "1_1") (pintype "passive"))
    )
    (net (code "95") (name "Net-(J11-3)") (class "Default")
      (node (ref "J11") (pin "P3") (pinfunction "3_P3") (pintype "passive"))
      (node (ref "R6") (pin "2") (pinfunction "2_2") (pintype "passive"))
    )
    (net (code "96") (name "Net-(J12-2)") (class "Default")
      (node (ref "J12") (pin "P2") (pinfunction "2_P2") (pintype "passive"))
      (node (ref "R64") (pin "1") (pinfunction "1_1") (pintype "passive"))
    )
    (net (code "97") (name "Net-(J12-3)") (class "Default")
      (node (ref "J12") (pin "P3") (pinfunction "3_P3") (pintype "passive"))
      (node (ref "R9") (pin "2") (pinfunction "2_2") (pintype "passive"))
    )
    (net (code "98") (name "Net-(JP1-Pad10)") (class "Default")
      (node (ref "JP1") (pin "10") (pinfunction "10_10") (pintype "passive"))
      (node (ref "JP1") (pin "9") (pinfunction "9_9") (pintype "passive"))
      (node (ref "P1") (pin "2") (pinfunction "2_2") (pintype "bidirectional"))
    )
    (net (code "99") (name "Net-(L1-Pad2)") (class "Default")
      (node (ref "L1") (pin "2") (pinfunction "2_2") (pintype "passive"))
      (node (ref "P1") (pin "1") (pinfunction "1_1") (pintype "bidirectional"))
    )
    (net (code "100") (name "Net-(R98A-A)") (class "Default")
      (node (ref "D6") (pin "C") (pinfunction "C_C") (pintype "passive"))
      (node (ref "R81") (pin "2") (pinfunction "2_2") (pintype "passive"))
      (node (ref "R98") (pin "B") (pinfunction "A_B") (pintype "passive"))
    )
    (net (code "101") (name "Net-(R98A-C)") (class "Default")
      (node (ref "D6") (pin "A") (pinfunction "A_A") (pintype "passive"))
      (node (ref "R13") (pin "1") (pinfunction "1_1") (pintype "passive"))
      (node (ref "R73") (pin "2") (pinfunction "2_2") (pintype "passive"))
      (node (ref "R98") (pin "E") (pinfunction "C_E") (pintype "passive"))
    )
    (net (code "102") (name "Net-(R98B-S)") (class "Default")
      (node (ref "R7") (pin "1") (pinfunction "1_1") (pintype "passive"))
      (node (ref "R98") (pin "2") (pinfunction "S_2") (pintype "passive"))
    )
    (net (code "103") (name "Net-(R99A-A)") (class "Default")
      (node (ref "D5") (pin "C") (pinfunction "C_C") (pintype "passive"))
      (node (ref "R79") (pin "2") (pinfunction "2_2") (pintype "passive"))
      (node (ref "R99") (pin "B") (pinfunction "A_B") (pintype "passive"))
    )
    (net (code "104") (name "Net-(R99A-C)") (class "Default")
      (node (ref "D5") (pin "A") (pinfunction "A_A") (pintype "passive"))
      (node (ref "R12") (pin "1") (pinfunction "1_1") (pintype "passive"))
      (node (ref "R72") (pin "2") (pinfunction "2_2") (pintype "passive"))
      (node (ref "R99") (pin "E") (pinfunction "C_E") (pintype "passive"))
    )
    (net (code "105") (name "Net-(R99B-S)") (class "Default")
      (node (ref "R8") (pin "1") (pinfunction "1_1") (pintype "passive"))
      (node (ref "R99") (pin "2") (pinfunction "S_2") (pintype "passive"))
    )
    (net (code "106") (name "Net-(R100A-A)") (class "Default")
      (node (ref "D4") (pin "C") (pinfunction "C_C") (pintype "passive"))
      (node (ref "R100") (pin "B") (pinfunction "A_B") (pintype "passive"))
      (node (ref "R78") (pin "2") (pinfunction "2_2") (pintype "passive"))
    )
    (net (code "107") (name "Net-(R100A-C)") (class "Default")
      (node (ref "D4") (pin "A") (pinfunction "A_A") (pintype "passive"))
      (node (ref "R10") (pin "1") (pinfunction "1_1") (pintype "passive"))
      (node (ref "R100") (pin "E") (pinfunction "C_E") (pintype "passive"))
      (node (ref "R70") (pin "2") (pinfunction "2_2") (pintype "passive"))
    )
    (net (code "108") (name "Net-(R100B-S)") (class "Default")
      (node (ref "R100") (pin "2") (pinfunction "S_2") (pintype "passive"))
      (node (ref "R6") (pin "1") (pinfunction "1_1") (pintype "passive"))
    )
    (net (code "109") (name "Net-(R101A-A)") (class "Default")
      (node (ref "D3") (pin "C") (pinfunction "C_C") (pintype "passive"))
      (node (ref "R101") (pin "B") (pinfunction "A_B") (pintype "passive"))
      (node (ref "R80") (pin "2") (pinfunction "2_2") (pintype "passive"))
    )
    (net (code "110") (name "Net-(R101A-C)") (class "Default")
      (node (ref "D3") (pin "A") (pinfunction "A_A") (pintype "passive"))
      (node (ref "R101") (pin "E") (pinfunction "C_E") (pintype "passive"))
      (node (ref "R11") (pin "1") (pinfunction "1_1") (pintype "passive"))
      (node (ref "R71") (pin "2") (pinfunction "2_2") (pintype "passive"))
    )
    (net (code "111") (name "Net-(R101B-S)") (class "Default")
      (node (ref "R101") (pin "2") (pinfunction "S_2") (pintype "passive"))
      (node (ref "R9") (pin "1") (pinfunction "1_1") (pintype "passive"))
    )
    (net (code "112") (name "Net-(R102-S)") (class "Default")
      (node (ref "C4") (pin "1") (pinfunction "1_1") (pintype "passive"))
      (node (ref "R102") (pin "P$2") (pinfunction "S_P$2") (pintype "passive"))
      (node (ref "R15") (pin "2") (pinfunction "2_2") (pintype "passive"))
    )
    (net (code "113") (name "Net-(R103-S)") (class "Default")
      (node (ref "C5") (pin "1") (pinfunction "1_1") (pintype "passive"))
      (node (ref "R103") (pin "P$2") (pinfunction "S_P$2") (pintype "passive"))
      (node (ref "R16") (pin "2") (pinfunction "2_2") (pintype "passive"))
    )
    (net (code "114") (name "Net-(R104-S)") (class "Default")
      (node (ref "C2") (pin "1") (pinfunction "1_1") (pintype "passive"))
      (node (ref "R104") (pin "P$2") (pinfunction "S_P$2") (pintype "passive"))
      (node (ref "R17") (pin "2") (pinfunction "2_2") (pintype "passive"))
    )
    (net (code "115") (name "Net-(R105-S)") (class "Default")
      (node (ref "C3") (pin "1") (pinfunction "1_1") (pintype "passive"))
      (node (ref "R105") (pin "P$2") (pinfunction "S_P$2") (pintype "passive"))
      (node (ref "R14") (pin "2") (pinfunction "2_2") (pintype "passive"))
    )
    (net (code "116") (name "Net-(R106-A)") (class "Default")
      (node (ref "R106") (pin "P$3") (pinfunction "A_P$3") (pintype "passive"))
      (node (ref "R4") (pin "2") (pinfunction "2_2") (pintype "passive"))
    )
    (net (code "117") (name "Net-(R107-A)") (class "Default")
      (node (ref "R107") (pin "P$3") (pinfunction "A_P$3") (pintype "passive"))
      (node (ref "R3") (pin "2") (pinfunction "2_2") (pintype "passive"))
    )
    (net (code "118") (name "Net-(R108-A)") (class "Default")
      (node (ref "R108") (pin "P$3") (pinfunction "A_P$3") (pintype "passive"))
      (node (ref "R2") (pin "2") (pinfunction "2_2") (pintype "passive"))
    )
    (net (code "119") (name "Net-(R109-A)") (class "Default")
      (node (ref "R1") (pin "2") (pinfunction "2_2") (pintype "passive"))
      (node (ref "R109") (pin "P$3") (pinfunction "A_P$3") (pintype "passive"))
    )
    (net (code "120") (name "VCC") (class "Default")
      (node (ref "C10") (pin "1") (pinfunction "1_1") (pintype "passive"))
      (node (ref "C11") (pin "1") (pinfunction "1_1") (pintype "passive"))
      (node (ref "C18") (pin "1") (pinfunction "1_1") (pintype "passive"))
      (node (ref "C19") (pin "1") (pinfunction "1_1") (pintype "passive"))
      (node (ref "C34") (pin "1") (pinfunction "1_1") (pintype "passive"))
      (node (ref "C35") (pin "1") (pinfunction "1_1") (pintype "passive"))
      (node (ref "C36") (pin "1") (pinfunction "1_1") (pintype "passive"))
      (node (ref "C37") (pin "1") (pinfunction "1_1") (pintype "passive"))
      (node (ref "C43") (pin "1") (pinfunction "1_1") (pintype "passive"))
      (node (ref "C45") (pin "1") (pinfunction "1_1") (pintype "passive"))
      (node (ref "C48") (pin "1") (pinfunction "1_1") (pintype "passive"))
      (node (ref "C50") (pin "1") (pinfunction "1_1") (pintype "passive"))
      (node (ref "IC10") (pin "4") (pinfunction "V+_4") (pintype "power_in"))
      (node (ref "IC2") (pin "4") (pinfunction "V+_4") (pintype "power_in"))
      (node (ref "IC3") (pin "4") (pinfunction "V+_4") (pintype "power_in"))
      (node (ref "IC4") (pin "16") (pinfunction "V+_16") (pintype "power_in"))
      (node (ref "IC5") (pin "16") (pinfunction "V+_16") (pintype "power_in"))
      (node (ref "IC6") (pin "4") (pinfunction "V+_4") (pintype "power_in"))
      (node (ref "IC7") (pin "4") (pinfunction "V+_4") (pintype "power_in"))
      (node (ref "IC9") (pin "4") (pinfunction "V+_4") (pintype "power_in"))
      (node (ref "L2") (pin "1") (pinfunction "1_1") (pintype "passive"))
      (node (ref "R33") (pin "1") (pinfunction "1_1") (pintype "passive"))
      (node (ref "R34") (pin "1") (pinfunction "1_1") (pintype "passive"))
      (node (ref "R69") (pin "1") (pinfunction "1_1") (pintype "passive"))
    )
    (net (code "121") (name "VEE") (class "Default")
      (node (ref "C12") (pin "2") (pinfunction "2_2") (pintype "passive"))
      (node (ref "C13") (pin "2") (pinfunction "2_2") (pintype "passive"))
      (node (ref "C26") (pin "2") (pinfunction "2_2") (pintype "passive"))
      (node (ref "C29") (pin "2") (pinfunction "2_2") (pintype "passive"))
      (node (ref "C38") (pin "2") (pinfunction "2_2") (pintype "passive"))
      (node (ref "C39") (pin "2") (pinfunction "2_2") (pintype "passive"))
      (node (ref "C44") (pin "2") (pinfunction "2_2") (pintype "passive"))
      (node (ref "C46") (pin "2") (pinfunction "2_2") (pintype "passive"))
      (node (ref "C47") (pin "2") (pinfunction "2_2") (pintype "passive"))
      (node (ref "C49") (pin "2") (pinfunction "2_2") (pintype "passive"))
      (node (ref "C6") (pin "2") (pinfunction "2_2") (pintype "passive"))
      (node (ref "C7") (pin "2") (pinfunction "2_2") (pintype "passive"))
      (node (ref "D1") (pin "A") (pinfunction "A_A") (pintype "passive"))
      (node (ref "IC10") (pin "11") (pinfunction "V-_11") (pintype "power_in"))
      (node (ref "IC2") (pin "11") (pinfunction "V-_11") (pintype "power_in"))
      (node (ref "IC3") (pin "11") (pinfunction "V-_11") (pintype "power_in"))
      (node (ref "IC4") (pin "9") (pinfunction "V-_9") (pintype "power_in"))
      (node (ref "IC5") (pin "9") (pinfunction "V-_9") (pintype "power_in"))
      (node (ref "IC6") (pin "11") (pinfunction "V-_11") (pintype "power_in"))
      (node (ref "IC7") (pin "11") (pinfunction "V-_11") (pintype "power_in"))
      (node (ref "IC9") (pin "11") (pinfunction "V-_11") (pintype "power_in"))
      (node (ref "L1") (pin "1") (pinfunction "1_1") (pintype "passive"))
      (node (ref "R5") (pin "1") (pinfunction "1_1") (pintype "passive"))
    )
    (net (code "122") (name "unconnected-(J4-2-PadP2)") (class "Default")
      (node (ref "J4") (pin "P2") (pinfunction "2_P2") (pintype "passive"))
    )
  )
)
